# RX8E_ulrich.net
KiCad netlist of a schematic drawn in EAGLE
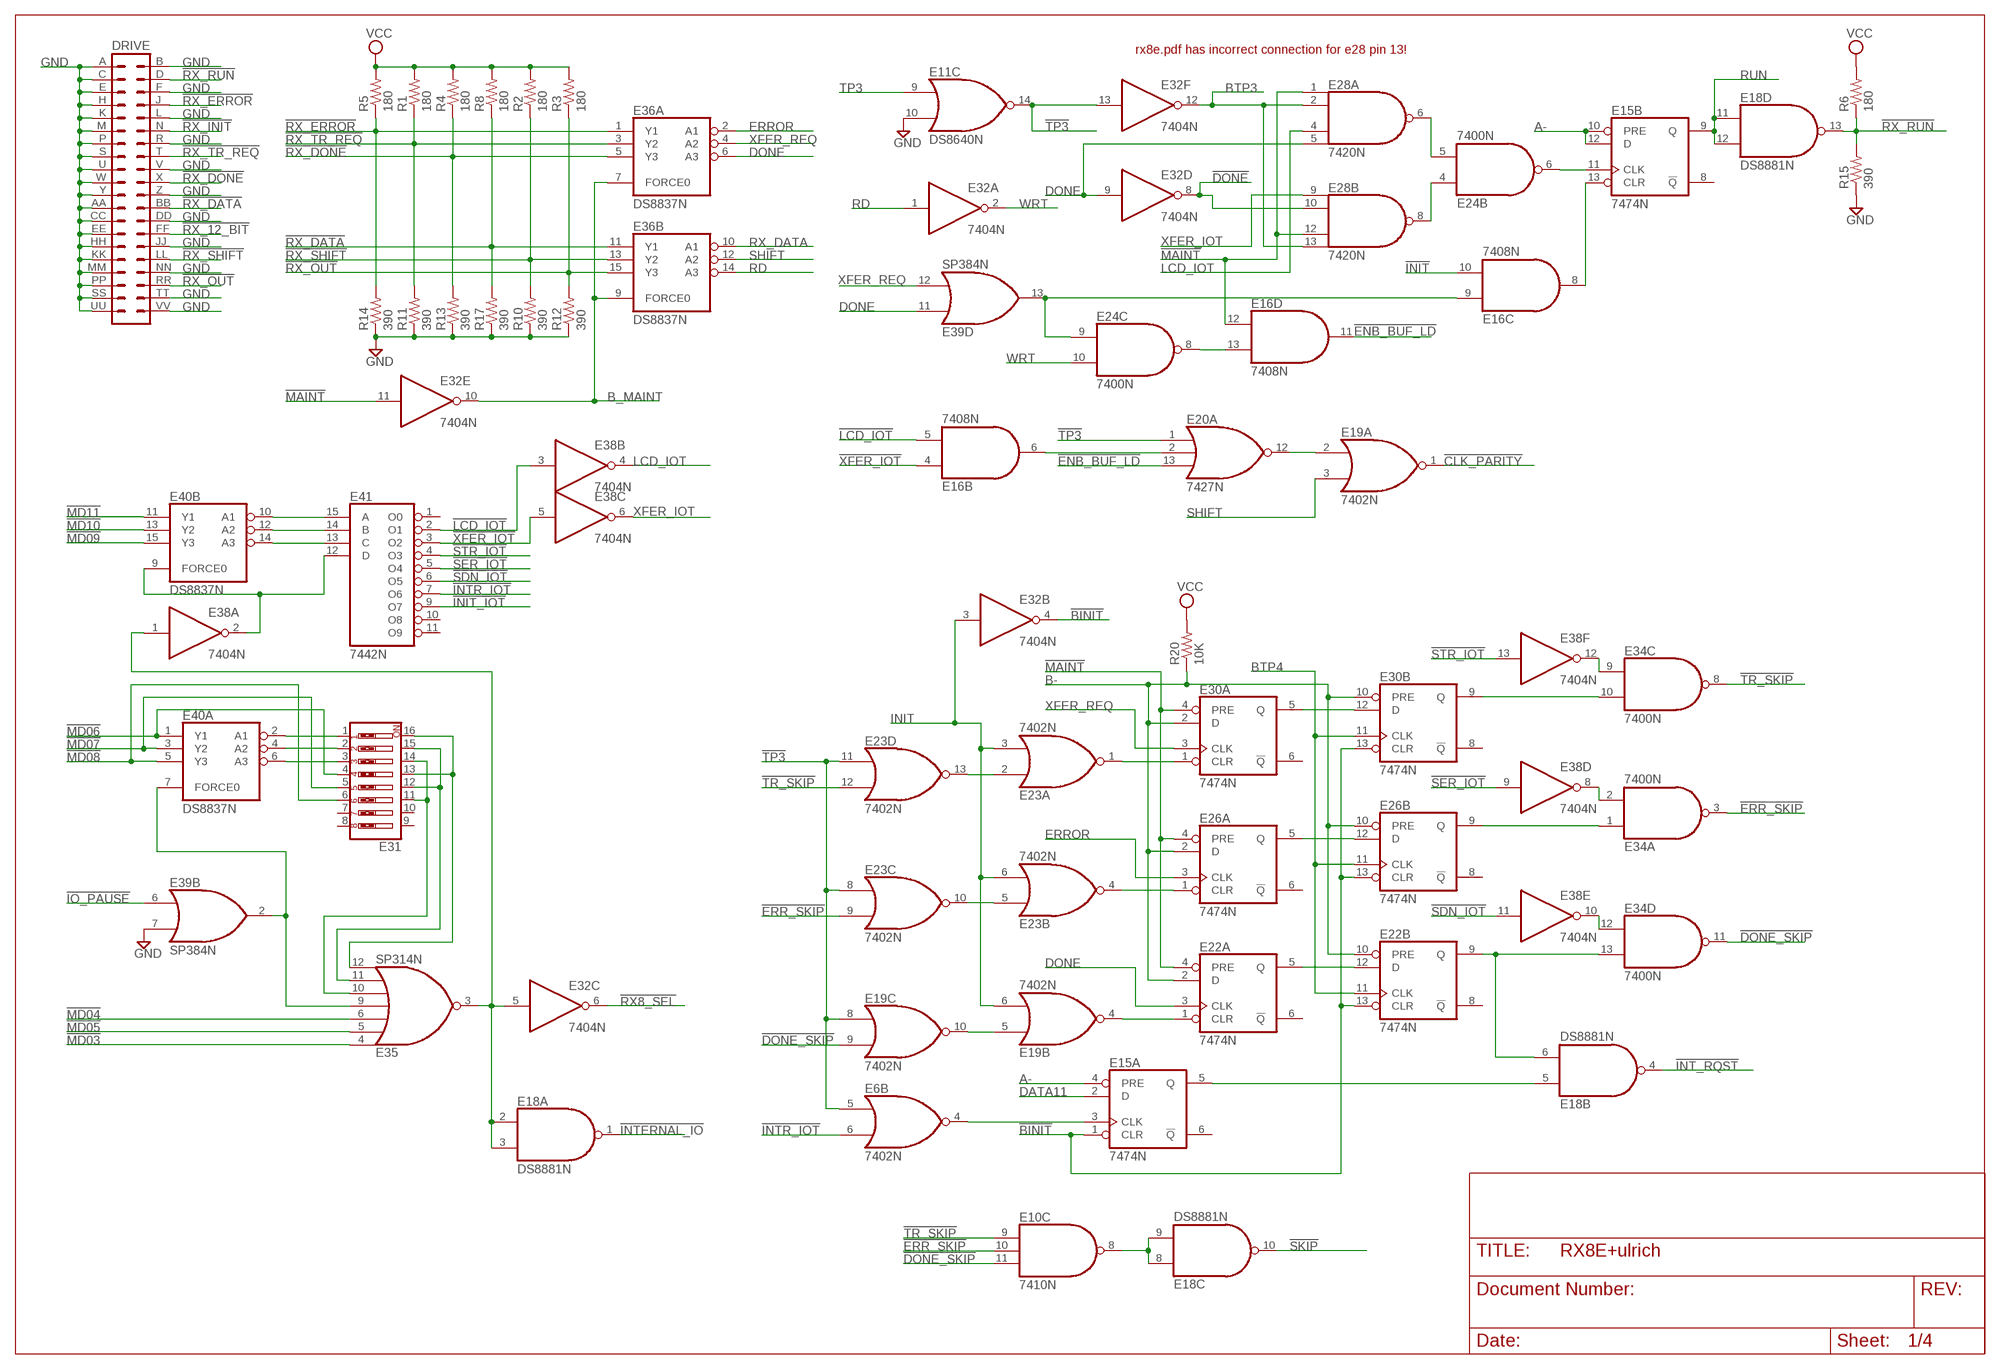
[diagram p0: schematic, sheet 1]
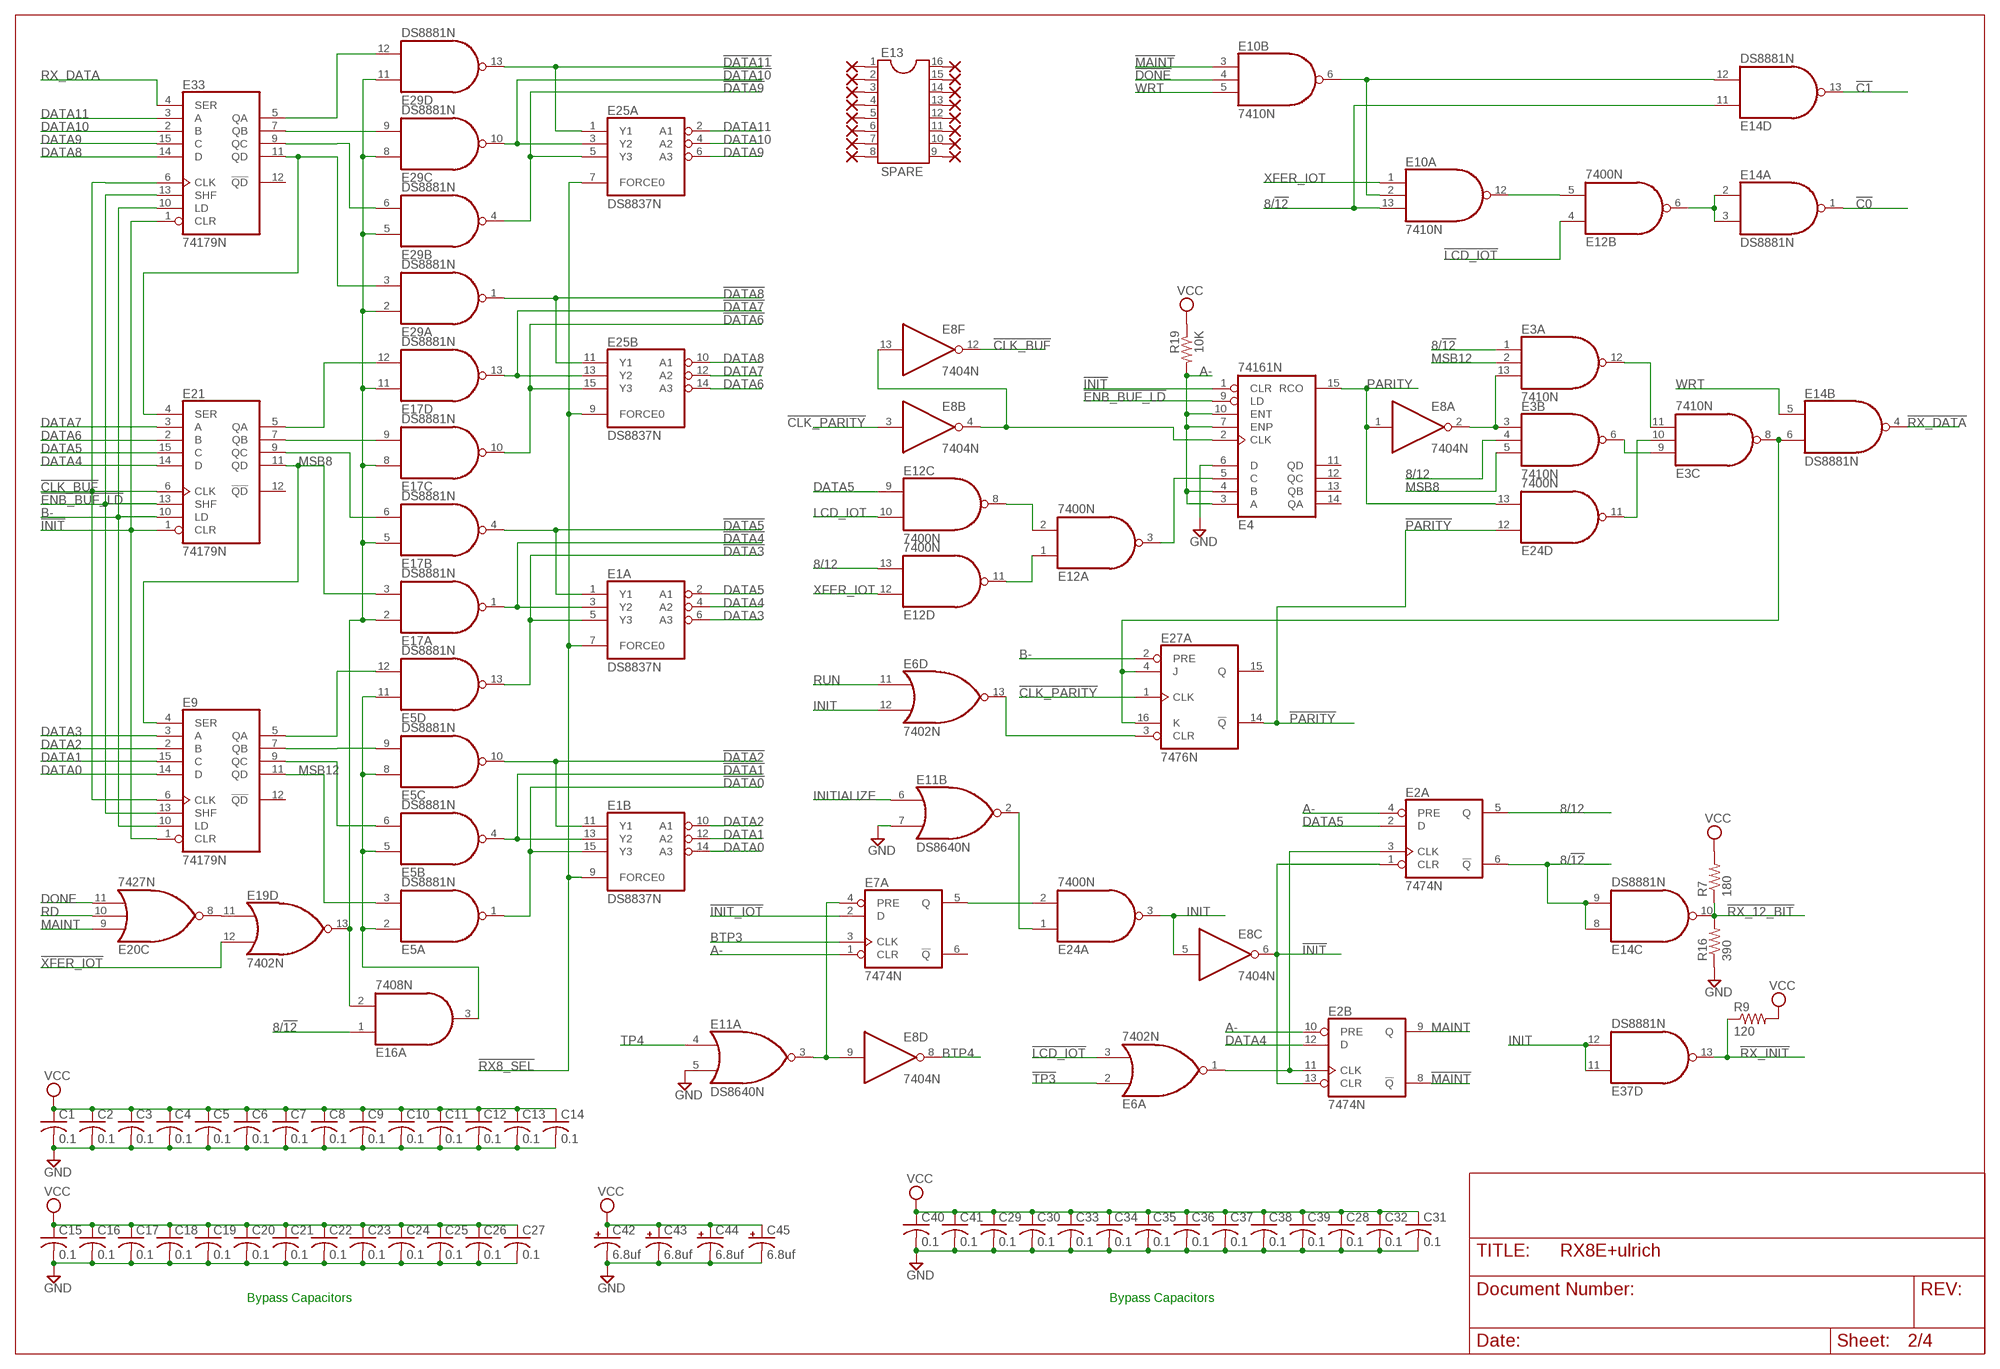
[diagram p1: schematic, sheet 2]
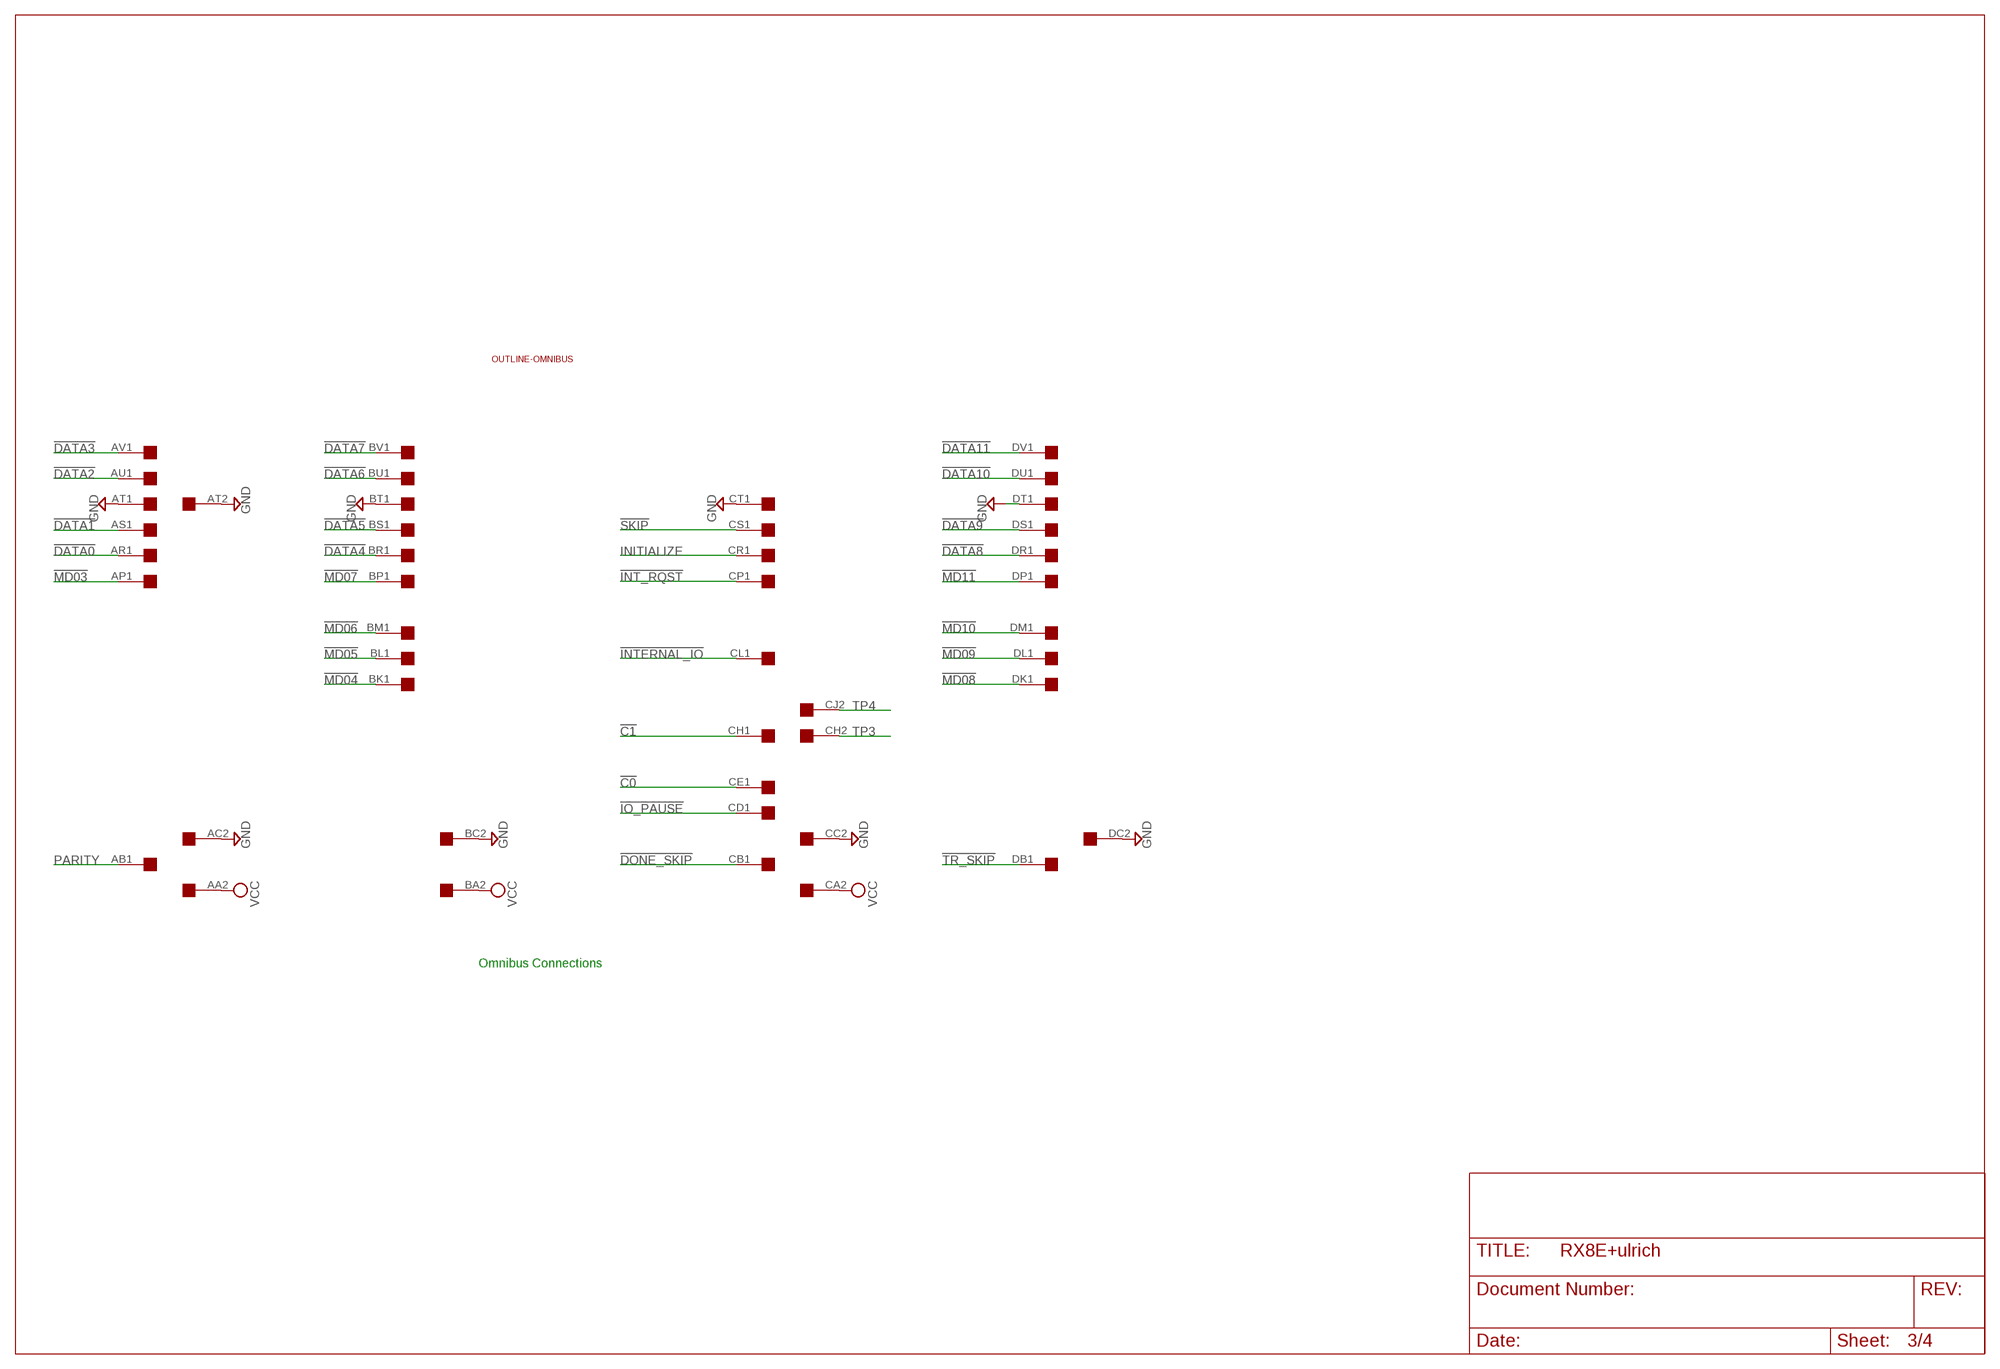
[diagram p2: schematic, sheet 3]
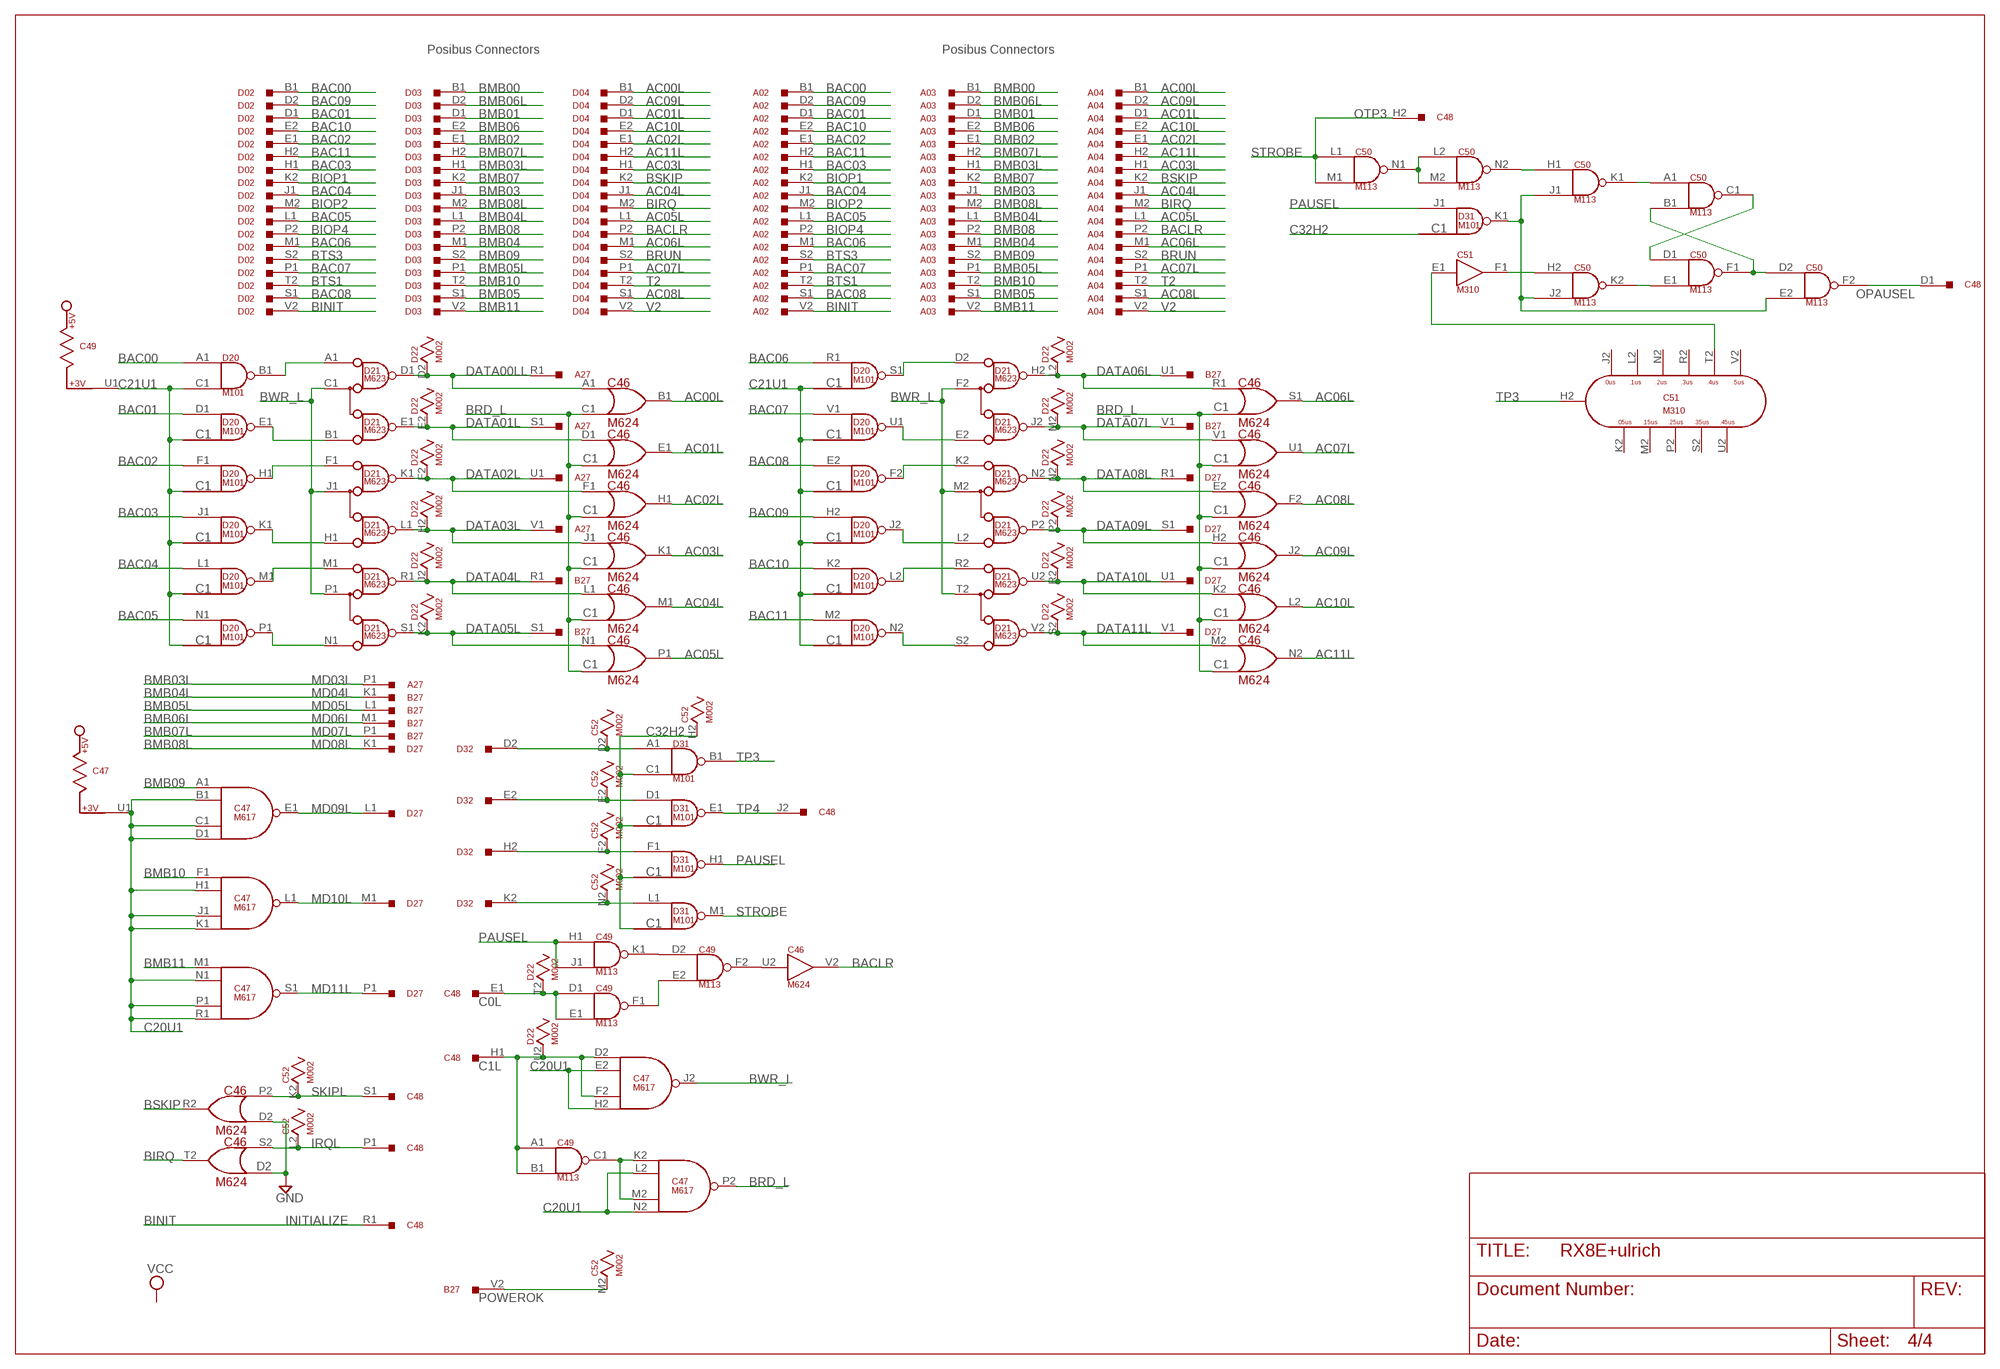
[diagram p3: schematic, sheet 4]

(export (version "E")
  (design (tool "Eeschema 10.0.6"))
  (components
    (comp (ref "C1")
      (value "0.1")
      (footprint "eagle-import:C050-025X075")
      (libsource (lib "eagle-import") (part "C-US050-025X075"))
    )
    (comp (ref "C2")
      (value "0.1")
      (footprint "eagle-import:C050-025X075")
      (libsource (lib "eagle-import") (part "C-US050-025X075"))
    )
    (comp (ref "C3")
      (value "0.1")
      (footprint "eagle-import:C050-025X075")
      (libsource (lib "eagle-import") (part "C-US050-025X075"))
    )
    (comp (ref "C4")
      (value "0.1")
      (footprint "eagle-import:C050-025X075")
      (libsource (lib "eagle-import") (part "C-US050-025X075"))
    )
    (comp (ref "C5")
      (value "0.1")
      (footprint "eagle-import:C050-025X075")
      (libsource (lib "eagle-import") (part "C-US050-025X075"))
    )
    (comp (ref "C6")
      (value "0.1")
      (footprint "eagle-import:C050-025X075")
      (libsource (lib "eagle-import") (part "C-US050-025X075"))
    )
    (comp (ref "C7")
      (value "0.1")
      (footprint "eagle-import:C050-025X075")
      (libsource (lib "eagle-import") (part "C-US050-025X075"))
    )
    (comp (ref "C8")
      (value "0.1")
      (footprint "eagle-import:C050-025X075")
      (libsource (lib "eagle-import") (part "C-US050-025X075"))
    )
    (comp (ref "C9")
      (value "0.1")
      (footprint "eagle-import:C050-025X075")
      (libsource (lib "eagle-import") (part "C-US050-025X075"))
    )
    (comp (ref "C10")
      (value "0.1")
      (footprint "eagle-import:C050-025X075")
      (libsource (lib "eagle-import") (part "C-US050-025X075"))
    )
    (comp (ref "C11")
      (value "0.1")
      (footprint "eagle-import:C050-025X075")
      (libsource (lib "eagle-import") (part "C-US050-025X075"))
    )
    (comp (ref "C12")
      (value "0.1")
      (footprint "eagle-import:C050-025X075")
      (libsource (lib "eagle-import") (part "C-US050-025X075"))
    )
    (comp (ref "C13")
      (value "0.1")
      (footprint "eagle-import:C050-025X075")
      (libsource (lib "eagle-import") (part "C-US050-025X075"))
    )
    (comp (ref "C14")
      (value "0.1")
      (footprint "eagle-import:C050-025X075")
      (libsource (lib "eagle-import") (part "C-US050-025X075"))
    )
    (comp (ref "C15")
      (value "0.1")
      (footprint "eagle-import:C050-025X075")
      (libsource (lib "eagle-import") (part "C-US050-025X075"))
    )
    (comp (ref "C16")
      (value "0.1")
      (footprint "eagle-import:C050-025X075")
      (libsource (lib "eagle-import") (part "C-US050-025X075"))
    )
    (comp (ref "C17")
      (value "0.1")
      (footprint "eagle-import:C050-025X075")
      (libsource (lib "eagle-import") (part "C-US050-025X075"))
    )
    (comp (ref "C18")
      (value "0.1")
      (footprint "eagle-import:C050-025X075")
      (libsource (lib "eagle-import") (part "C-US050-025X075"))
    )
    (comp (ref "C19")
      (value "0.1")
      (footprint "eagle-import:C050-025X075")
      (libsource (lib "eagle-import") (part "C-US050-025X075"))
    )
    (comp (ref "C20")
      (value "0.1")
      (footprint "eagle-import:C050-025X075")
      (libsource (lib "eagle-import") (part "C-US050-025X075"))
    )
    (comp (ref "C21")
      (value "0.1")
      (footprint "eagle-import:C050-025X075")
      (libsource (lib "eagle-import") (part "C-US050-025X075"))
    )
    (comp (ref "C22")
      (value "0.1")
      (footprint "eagle-import:C050-025X075")
      (libsource (lib "eagle-import") (part "C-US050-025X075"))
    )
    (comp (ref "C23")
      (value "0.1")
      (footprint "eagle-import:C050-025X075")
      (libsource (lib "eagle-import") (part "C-US050-025X075"))
    )
    (comp (ref "C24")
      (value "0.1")
      (footprint "eagle-import:C050-025X075")
      (libsource (lib "eagle-import") (part "C-US050-025X075"))
    )
    (comp (ref "C25")
      (value "0.1")
      (footprint "eagle-import:C050-025X075")
      (libsource (lib "eagle-import") (part "C-US050-025X075"))
    )
    (comp (ref "C26")
      (value "0.1")
      (footprint "eagle-import:C050-025X075")
      (libsource (lib "eagle-import") (part "C-US050-025X075"))
    )
    (comp (ref "C27")
      (value "0.1")
      (footprint "eagle-import:C050-025X075")
      (libsource (lib "eagle-import") (part "C-US050-025X075"))
    )
    (comp (ref "C28")
      (value "0.1")
      (footprint "eagle-import:C050-025X075")
      (libsource (lib "eagle-import") (part "C-US050-025X075"))
    )
    (comp (ref "C29")
      (value "0.1")
      (footprint "eagle-import:C050-025X075")
      (libsource (lib "eagle-import") (part "C-US050-025X075"))
    )
    (comp (ref "C30")
      (value "0.1")
      (footprint "eagle-import:C050-025X075")
      (libsource (lib "eagle-import") (part "C-US050-025X075"))
    )
    (comp (ref "C31")
      (value "0.1")
      (footprint "eagle-import:C050-025X075")
      (libsource (lib "eagle-import") (part "C-US050-025X075"))
    )
    (comp (ref "C32")
      (value "0.1")
      (footprint "eagle-import:C050-025X075")
      (libsource (lib "eagle-import") (part "C-US050-025X075"))
    )
    (comp (ref "C33")
      (value "0.1")
      (footprint "eagle-import:C050-025X075")
      (libsource (lib "eagle-import") (part "C-US050-025X075"))
    )
    (comp (ref "C34")
      (value "0.1")
      (footprint "eagle-import:C050-025X075")
      (libsource (lib "eagle-import") (part "C-US050-025X075"))
    )
    (comp (ref "C35")
      (value "0.1")
      (footprint "eagle-import:C050-025X075")
      (libsource (lib "eagle-import") (part "C-US050-025X075"))
    )
    (comp (ref "C36")
      (value "0.1")
      (footprint "eagle-import:C050-025X075")
      (libsource (lib "eagle-import") (part "C-US050-025X075"))
    )
    (comp (ref "C37")
      (value "0.1")
      (footprint "eagle-import:C050-025X075")
      (libsource (lib "eagle-import") (part "C-US050-025X075"))
    )
    (comp (ref "C38")
      (value "0.1")
      (footprint "eagle-import:C050-025X075")
      (libsource (lib "eagle-import") (part "C-US050-025X075"))
    )
    (comp (ref "C39")
      (value "0.1")
      (footprint "eagle-import:C050-025X075")
      (libsource (lib "eagle-import") (part "C-US050-025X075"))
    )
    (comp (ref "C40")
      (value "0.1")
      (footprint "eagle-import:C050-025X075")
      (libsource (lib "eagle-import") (part "C-US050-025X075"))
    )
    (comp (ref "C41")
      (value "0.1")
      (footprint "eagle-import:C050-025X075")
      (libsource (lib "eagle-import") (part "C-US050-025X075"))
    )
    (comp (ref "C42")
      (value "6.8uf")
      (footprint "eagle-import:E22-6")
      (libsource (lib "eagle-import") (part "CPOL-USE22-6AXIAL"))
    )
    (comp (ref "C43")
      (value "6.8uf")
      (footprint "eagle-import:E22-6")
      (libsource (lib "eagle-import") (part "CPOL-USE22-6AXIAL"))
    )
    (comp (ref "C44")
      (value "6.8uf")
      (footprint "eagle-import:E22-6")
      (libsource (lib "eagle-import") (part "CPOL-USE22-6AXIAL"))
    )
    (comp (ref "C45")
      (value "6.8uf")
      (footprint "eagle-import:E22-6")
      (libsource (lib "eagle-import") (part "CPOL-USE22-6AXIAL"))
    )
    (comp (ref "E1")
      (value "DS8837N")
      (footprint "eagle-import:DIL16")
      (libsource (lib "eagle-import") (part "DS8837N"))
    )
    (comp (ref "E2")
      (value "7474N")
      (footprint "eagle-import:DIL14")
      (libsource (lib "eagle-import") (part "7474NLS"))
    )
    (comp (ref "E3")
      (value "7410N")
      (footprint "eagle-import:DIL14")
      (libsource (lib "eagle-import") (part "7410NLS"))
    )
    (comp (ref "E4")
      (value "74161N")
      (footprint "eagle-import:DIL16")
      (libsource (lib "eagle-import") (part "74161N"))
    )
    (comp (ref "E5")
      (value "DS8881N")
      (footprint "eagle-import:DIL14")
      (libsource (lib "eagle-import") (part "7401NLS"))
    )
    (comp (ref "E6")
      (value "7402N")
      (footprint "eagle-import:DIL14")
      (libsource (lib "eagle-import") (part "7402NLS"))
    )
    (comp (ref "E7")
      (value "7474N")
      (footprint "eagle-import:DIL14")
      (libsource (lib "eagle-import") (part "7474NLS"))
    )
    (comp (ref "E8")
      (value "7404N")
      (footprint "eagle-import:DIL14")
      (libsource (lib "eagle-import") (part "7404NLS"))
    )
    (comp (ref "E9")
      (value "74179N")
      (footprint "eagle-import:DIL16")
      (libsource (lib "eagle-import") (part "74179N"))
    )
    (comp (ref "E10")
      (value "7410N")
      (footprint "eagle-import:DIL14")
      (libsource (lib "eagle-import") (part "7410NLS"))
    )
    (comp (ref "E11")
      (value "DS8640N")
      (footprint "eagle-import:DIL14")
      (libsource (lib "eagle-import") (part "DS8640N"))
    )
    (comp (ref "E12")
      (value "7400N")
      (footprint "eagle-import:DIL14")
      (libsource (lib "eagle-import") (part "7400NLS"))
    )
    (comp (ref "E13")
      (value "SPARE")
      (footprint "eagle-import:DIL16")
      (libsource (lib "eagle-import") (part "DIL16"))
    )
    (comp (ref "E14")
      (value "DS8881N")
      (footprint "eagle-import:DIL14")
      (libsource (lib "eagle-import") (part "7401NLS"))
    )
    (comp (ref "E16")
      (value "7408N")
      (footprint "eagle-import:DIL14")
      (libsource (lib "eagle-import") (part "7408NLS"))
    )
    (comp (ref "E17")
      (value "DS8881N")
      (footprint "eagle-import:DIL14")
      (libsource (lib "eagle-import") (part "7401NLS"))
    )
    (comp (ref "E19")
      (value "7402N")
      (footprint "eagle-import:DIL14")
      (libsource (lib "eagle-import") (part "7402NLS"))
    )
    (comp (ref "E20")
      (value "7427N")
      (footprint "eagle-import:DIL14")
      (libsource (lib "eagle-import") (part "7427NLS"))
    )
    (comp (ref "E21")
      (value "74179N")
      (footprint "eagle-import:DIL16")
      (libsource (lib "eagle-import") (part "74179N"))
    )
    (comp (ref "E24")
      (value "7400N")
      (footprint "eagle-import:DIL14")
      (libsource (lib "eagle-import") (part "7400NLS"))
    )
    (comp (ref "E25")
      (value "DS8837N")
      (footprint "eagle-import:DIL16")
      (libsource (lib "eagle-import") (part "DS8837N"))
    )
    (comp (ref "E27")
      (value "7476N")
      (footprint "eagle-import:DIL16")
      (libsource (lib "eagle-import") (part "7476N"))
    )
    (comp (ref "E29")
      (value "DS8881N")
      (footprint "eagle-import:DIL14")
      (libsource (lib "eagle-import") (part "7401NLS"))
    )
    (comp (ref "E33")
      (value "74179N")
      (footprint "eagle-import:DIL16")
      (libsource (lib "eagle-import") (part "74179N"))
    )
    (comp (ref "E37")
      (value "DS8881N")
      (footprint "eagle-import:DIL14")
      (libsource (lib "eagle-import") (part "7401NLS"))
    )
    (comp (ref "PAD10")
      (value "1,6/0,8")
      (footprint "eagle-import:1,6_0,8")
      (libsource (lib "eagle-import") (part "1,6/0,8"))
    )
    (comp (ref "PAD11")
      (value "1,6/0,8")
      (footprint "eagle-import:1,6_0,8")
      (libsource (lib "eagle-import") (part "1,6/0,8"))
    )
    (comp (ref "PAD12")
      (value "1,6/0,8")
      (footprint "eagle-import:1,6_0,8")
      (libsource (lib "eagle-import") (part "1,6/0,8"))
    )
    (comp (ref "PAD13")
      (value "1,6/0,8")
      (footprint "eagle-import:1,6_0,8")
      (libsource (lib "eagle-import") (part "1,6/0,8"))
    )
    (comp (ref "PAD14")
      (value "1,6/0,8")
      (footprint "eagle-import:1,6_0,8")
      (libsource (lib "eagle-import") (part "1,6/0,8"))
    )
    (comp (ref "PAD15")
      (value "1,6/0,8")
      (footprint "eagle-import:1,6_0,8")
      (libsource (lib "eagle-import") (part "1,6/0,8"))
    )
    (comp (ref "PAD16")
      (value "1,6/0,8")
      (footprint "eagle-import:1,6_0,8")
      (libsource (lib "eagle-import") (part "1,6/0,8"))
    )
    (comp (ref "PAD17")
      (value "1,6/0,8")
      (footprint "eagle-import:1,6_0,8")
      (libsource (lib "eagle-import") (part "1,6/0,8"))
    )
    (comp (ref "PAD20")
      (value "1,6/0,8")
      (footprint "eagle-import:1,6_0,8")
      (libsource (lib "eagle-import") (part "1,6/0,8"))
    )
    (comp (ref "PAD21")
      (value "1,6/0,8")
      (footprint "eagle-import:1,6_0,8")
      (libsource (lib "eagle-import") (part "1,6/0,8"))
    )
    (comp (ref "PAD22")
      (value "1,6/0,8")
      (footprint "eagle-import:1,6_0,8")
      (libsource (lib "eagle-import") (part "1,6/0,8"))
    )
    (comp (ref "PAD23")
      (value "1,6/0,8")
      (footprint "eagle-import:1,6_0,8")
      (libsource (lib "eagle-import") (part "1,6/0,8"))
    )
    (comp (ref "PAD24")
      (value "1,6/0,8")
      (footprint "eagle-import:1,6_0,8")
      (libsource (lib "eagle-import") (part "1,6/0,8"))
    )
    (comp (ref "PAD25")
      (value "1,6/0,8")
      (footprint "eagle-import:1,6_0,8")
      (libsource (lib "eagle-import") (part "1,6/0,8"))
    )
    (comp (ref "PAD26")
      (value "1,6/0,8")
      (footprint "eagle-import:1,6_0,8")
      (libsource (lib "eagle-import") (part "1,6/0,8"))
    )
    (comp (ref "PAD27")
      (value "1,6/0,8")
      (footprint "eagle-import:1,6_0,8")
      (libsource (lib "eagle-import") (part "1,6/0,8"))
    )
    (comp (ref "R7")
      (value "180")
      (footprint "eagle-import:0207_10")
      (libsource (lib "eagle-import") (part "R-US_0207/10"))
    )
    (comp (ref "R9")
      (value "120")
      (footprint "eagle-import:0207_10")
      (libsource (lib "eagle-import") (part "R-US_0207/10"))
    )
    (comp (ref "R16")
      (value "390")
      (footprint "eagle-import:0207_10")
      (libsource (lib "eagle-import") (part "R-US_0207/10"))
    )
    (comp (ref "R19")
      (value "10K")
      (footprint "eagle-import:0207_10")
      (libsource (lib "eagle-import") (part "R-US_0207/10"))
    )
    (comp (ref "U$2")
      (value "QUAD")
      (footprint "eagle-import:EDGE-CON8")
      (libsource (lib "eagle-import") (part "QUAD"))
    )
    (comp (ref "U$5")
      (value "OUTLINE-OMNIBUS")
      (footprint "eagle-import:OMNIBUS")
      (libsource (lib "eagle-import") (part "OUTLINE-OMNIBUS"))
    )
    (comp (ref "DRIVE")
      (value "DEC40PINH")
      (footprint "eagle-import:DEC40PINH")
      (libsource (lib "eagle-import") (part "DEC40PINH"))
    )
    (comp (ref "E15")
      (value "7474N")
      (footprint "eagle-import:DIL14")
      (libsource (lib "eagle-import") (part "7474NLS"))
    )
    (comp (ref "E18")
      (value "DS8881N")
      (footprint "eagle-import:DIL14")
      (libsource (lib "eagle-import") (part "7401NLS"))
    )
    (comp (ref "E22")
      (value "7474N")
      (footprint "eagle-import:DIL14")
      (libsource (lib "eagle-import") (part "7474NLS"))
    )
    (comp (ref "E23")
      (value "7402N")
      (footprint "eagle-import:DIL14")
      (libsource (lib "eagle-import") (part "7402NLS"))
    )
    (comp (ref "E26")
      (value "7474N")
      (footprint "eagle-import:DIL14")
      (libsource (lib "eagle-import") (part "7474NLS"))
    )
    (comp (ref "E28")
      (value "7420N")
      (footprint "eagle-import:DIL14")
      (libsource (lib "eagle-import") (part "7420NLS"))
    )
    (comp (ref "E30")
      (value "7474N")
      (footprint "eagle-import:DIL14")
      (libsource (lib "eagle-import") (part "7474NLS"))
    )
    (comp (ref "E31")
      (value "SW_DIP-8")
      (footprint "eagle-import:EDG-08")
      (libsource (lib "eagle-import") (part "SW_DIP-8"))
    )
    (comp (ref "E32")
      (value "7404N")
      (footprint "eagle-import:DIL14")
      (libsource (lib "eagle-import") (part "7404NLS"))
    )
    (comp (ref "E34")
      (value "7400N")
      (footprint "eagle-import:DIL14")
      (libsource (lib "eagle-import") (part "7400N"))
    )
    (comp (ref "E35")
      (value "SP314N")
      (footprint "eagle-import:DIL14")
      (libsource (lib "eagle-import") (part "SP314N"))
    )
    (comp (ref "E36")
      (value "DS8837N")
      (footprint "eagle-import:DIL16")
      (libsource (lib "eagle-import") (part "DS8837N"))
    )
    (comp (ref "E38")
      (value "7404N")
      (footprint "eagle-import:DIL14")
      (libsource (lib "eagle-import") (part "7404NLS"))
    )
    (comp (ref "E39")
      (value "SP384N")
      (footprint "eagle-import:DIL14")
      (libsource (lib "eagle-import") (part "SP384N"))
    )
    (comp (ref "E40")
      (value "DS8837N")
      (footprint "eagle-import:DIL16")
      (libsource (lib "eagle-import") (part "DS8837N"))
    )
    (comp (ref "E41")
      (value "7442N")
      (footprint "eagle-import:DIL16")
      (libsource (lib "eagle-import") (part "7442NLS"))
    )
    (comp (ref "R1")
      (value "180")
      (footprint "eagle-import:0207_10")
      (libsource (lib "eagle-import") (part "R-US_0207/10"))
    )
    (comp (ref "R2")
      (value "180")
      (footprint "eagle-import:0207_10")
      (libsource (lib "eagle-import") (part "R-US_0207/10"))
    )
    (comp (ref "R3")
      (value "180")
      (footprint "eagle-import:0207_10")
      (libsource (lib "eagle-import") (part "R-US_0207/10"))
    )
    (comp (ref "R4")
      (value "180")
      (footprint "eagle-import:0207_10")
      (libsource (lib "eagle-import") (part "R-US_0207/10"))
    )
    (comp (ref "R5")
      (value "180")
      (footprint "eagle-import:0207_10")
      (libsource (lib "eagle-import") (part "R-US_0207/10"))
    )
    (comp (ref "R6")
      (value "180")
      (footprint "eagle-import:0207_10")
      (libsource (lib "eagle-import") (part "R-US_0207/10"))
    )
    (comp (ref "R8")
      (value "180")
      (footprint "eagle-import:0207_10")
      (libsource (lib "eagle-import") (part "R-US_0207/10"))
    )
    (comp (ref "R10")
      (value "390")
      (footprint "eagle-import:0207_10")
      (libsource (lib "eagle-import") (part "R-US_0207/10"))
    )
    (comp (ref "R11")
      (value "390")
      (footprint "eagle-import:0207_10")
      (libsource (lib "eagle-import") (part "R-US_0207/10"))
    )
    (comp (ref "R12")
      (value "390")
      (footprint "eagle-import:0207_10")
      (libsource (lib "eagle-import") (part "R-US_0207/10"))
    )
    (comp (ref "R13")
      (value "390")
      (footprint "eagle-import:0207_10")
      (libsource (lib "eagle-import") (part "R-US_0207/10"))
    )
    (comp (ref "R14")
      (value "390")
      (footprint "eagle-import:0207_10")
      (libsource (lib "eagle-import") (part "R-US_0207/10"))
    )
    (comp (ref "R15")
      (value "390")
      (footprint "eagle-import:0207_10")
      (libsource (lib "eagle-import") (part "R-US_0207/10"))
    )
    (comp (ref "R17")
      (value "390")
      (footprint "eagle-import:0207_10")
      (libsource (lib "eagle-import") (part "R-US_0207/10"))
    )
    (comp (ref "R20")
      (value "10K")
      (footprint "eagle-import:0207_10")
      (libsource (lib "eagle-import") (part "R-US_0207/10"))
    )
    (comp (ref "A02")
      (value "M903")
      (footprint "eagle-import:H807")
      (libsource (lib "eagle-import") (part "M903"))
    )
    (comp (ref "A03")
      (value "M903")
      (footprint "eagle-import:H807")
      (libsource (lib "eagle-import") (part "M903"))
    )
    (comp (ref "A04")
      (value "M903")
      (footprint "eagle-import:H807")
      (libsource (lib "eagle-import") (part "M903"))
    )
    (comp (ref "A27")
      (value "M916")
      (footprint "eagle-import:H807")
      (libsource (lib "eagle-import") (part "M916"))
    )
    (comp (ref "B27")
      (value "M916")
      (footprint "eagle-import:H807")
      (libsource (lib "eagle-import") (part "M916"))
    )
    (comp (ref "C46")
      (value "M624")
      (footprint "eagle-import:H807")
      (libsource (lib "eagle-import") (part "M624"))
    )
    (comp (ref "C47")
      (value "M617")
      (footprint "eagle-import:H807")
      (libsource (lib "eagle-import") (part "M617"))
    )
    (comp (ref "C48")
      (value "M916")
      (footprint "eagle-import:H807")
      (libsource (lib "eagle-import") (part "M916"))
    )
    (comp (ref "C49")
      (value "M113")
      (footprint "eagle-import:H807")
      (libsource (lib "eagle-import") (part "M113"))
    )
    (comp (ref "C50")
      (value "M113")
      (footprint "eagle-import:H807")
      (libsource (lib "eagle-import") (part "M113"))
    )
    (comp (ref "C51")
      (value "M310")
      (footprint "eagle-import:H807")
      (libsource (lib "eagle-import") (part "M310"))
    )
    (comp (ref "C52")
      (value "M002")
      (footprint "eagle-import:H807")
      (libsource (lib "eagle-import") (part "M002"))
    )
    (comp (ref "D02")
      (value "M903")
      (footprint "eagle-import:H807")
      (libsource (lib "eagle-import") (part "M903"))
    )
    (comp (ref "D03")
      (value "M903")
      (footprint "eagle-import:H807")
      (libsource (lib "eagle-import") (part "M903"))
    )
    (comp (ref "D04")
      (value "M903")
      (footprint "eagle-import:H807")
      (libsource (lib "eagle-import") (part "M903"))
    )
    (comp (ref "D20")
      (value "M101")
      (footprint "eagle-import:H807")
      (libsource (lib "eagle-import") (part "M101"))
    )
    (comp (ref "D21")
      (value "M623")
      (footprint "eagle-import:H807")
      (libsource (lib "eagle-import") (part "M623"))
    )
    (comp (ref "D22")
      (value "M002")
      (footprint "eagle-import:H807")
      (libsource (lib "eagle-import") (part "M002"))
    )
    (comp (ref "D27")
      (value "M916")
      (footprint "eagle-import:H807")
      (libsource (lib "eagle-import") (part "M916"))
    )
    (comp (ref "D31")
      (value "M101")
      (footprint "eagle-import:H807")
      (libsource (lib "eagle-import") (part "M101"))
    )
    (comp (ref "D32")
      (value "M903")
      (footprint "eagle-import:H807")
      (libsource (lib "eagle-import") (part "M903"))
    )
  )
  (nets
    (net (code "1") (name "8{slash}12") (class "Default")
      (node (ref "E12") (pin "13") (pinfunction "I1_13") (pintype "input"))
      (node (ref "E2") (pin "5") (pinfunction "Q_5") (pintype "output"))
      (node (ref "E3") (pin "4") (pinfunction "I1_4") (pintype "input"))
    )
    (net (code "2") (name "8{slash}~{12}") (class "Default")
      (node (ref "E10") (pin "13") (pinfunction "I2_13") (pintype "input"))
      (node (ref "E14") (pin "11") (pinfunction "I0_11") (pintype "input"))
      (node (ref "E14") (pin "8") (pinfunction "I0_8") (pintype "input"))
      (node (ref "E14") (pin "9") (pinfunction "I1_9") (pintype "input"))
      (node (ref "E16") (pin "1") (pinfunction "I0_1") (pintype "input"))
      (node (ref "E2") (pin "6") (pinfunction "~{Q}_6") (pintype "output"))
      (node (ref "E3") (pin "1") (pinfunction "I0_1") (pintype "input"))
    )
    (net (code "3") (name "A-") (class "Default")
      (node (ref "E15") (pin "10") (pinfunction "PRE_10") (pintype "input"))
      (node (ref "E15") (pin "12") (pinfunction "D_12") (pintype "input"))
      (node (ref "E15") (pin "4") (pinfunction "PRE_4") (pintype "input"))
      (node (ref "E2") (pin "10") (pinfunction "PRE_10") (pintype "input"))
      (node (ref "E2") (pin "4") (pinfunction "PRE_4") (pintype "input"))
      (node (ref "E4") (pin "10") (pinfunction "ENT_10") (pintype "input"))
      (node (ref "E4") (pin "3") (pinfunction "A_3") (pintype "input"))
      (node (ref "E4") (pin "4") (pinfunction "B_4") (pintype "input"))
      (node (ref "E4") (pin "7") (pinfunction "ENP_7") (pintype "input"))
      (node (ref "E7") (pin "1") (pinfunction "CLR_1") (pintype "input"))
      (node (ref "R19") (pin "2") (pinfunction "2_2") (pintype "passive"))
    )
    (net (code "4") (name "AC00L") (class "Default")
      (node (ref "A04") (pin "B1") (pinfunction "P$2_B1") (pintype "bidirectional"))
      (node (ref "C46") (pin "B1") (pinfunction "OUT_B1") (pintype "output"))
      (node (ref "D04") (pin "B1") (pinfunction "P$2_B1") (pintype "bidirectional"))
    )
    (net (code "5") (name "AC01L") (class "Default")
      (node (ref "A04") (pin "D1") (pinfunction "P$2_D1") (pintype "bidirectional"))
      (node (ref "C46") (pin "E1") (pinfunction "OUT_E1") (pintype "output"))
      (node (ref "D04") (pin "D1") (pinfunction "P$2_D1") (pintype "bidirectional"))
    )
    (net (code "6") (name "AC02L") (class "Default")
      (node (ref "A04") (pin "E1") (pinfunction "P$2_E1") (pintype "bidirectional"))
      (node (ref "C46") (pin "H1") (pinfunction "OUT_H1") (pintype "output"))
      (node (ref "D04") (pin "E1") (pinfunction "P$2_E1") (pintype "bidirectional"))
    )
    (net (code "7") (name "AC03L") (class "Default")
      (node (ref "A04") (pin "H1") (pinfunction "P$2_H1") (pintype "bidirectional"))
      (node (ref "C46") (pin "K1") (pinfunction "OUT_K1") (pintype "output"))
      (node (ref "D04") (pin "H1") (pinfunction "P$2_H1") (pintype "bidirectional"))
    )
    (net (code "8") (name "AC04L") (class "Default")
      (node (ref "A04") (pin "J1") (pinfunction "P$2_J1") (pintype "bidirectional"))
      (node (ref "C46") (pin "M1") (pinfunction "OUT_M1") (pintype "output"))
      (node (ref "D04") (pin "J1") (pinfunction "P$2_J1") (pintype "bidirectional"))
    )
    (net (code "9") (name "AC05L") (class "Default")
      (node (ref "A04") (pin "L1") (pinfunction "P$2_L1") (pintype "bidirectional"))
      (node (ref "C46") (pin "P1") (pinfunction "OUT_P1") (pintype "output"))
      (node (ref "D04") (pin "L1") (pinfunction "P$2_L1") (pintype "bidirectional"))
    )
    (net (code "10") (name "AC06L") (class "Default")
      (node (ref "A04") (pin "M1") (pinfunction "P$2_M1") (pintype "bidirectional"))
      (node (ref "C46") (pin "S1") (pinfunction "OUT_S1") (pintype "output"))
      (node (ref "D04") (pin "M1") (pinfunction "P$2_M1") (pintype "bidirectional"))
    )
    (net (code "11") (name "AC07L") (class "Default")
      (node (ref "A04") (pin "P1") (pinfunction "P$2_P1") (pintype "bidirectional"))
      (node (ref "C46") (pin "U1") (pinfunction "OUT_U1") (pintype "output"))
      (node (ref "D04") (pin "P1") (pinfunction "P$2_P1") (pintype "bidirectional"))
    )
    (net (code "12") (name "AC08L") (class "Default")
      (node (ref "A04") (pin "S1") (pinfunction "P$2_S1") (pintype "bidirectional"))
      (node (ref "C46") (pin "F2") (pinfunction "OUT_F2") (pintype "output"))
      (node (ref "D04") (pin "S1") (pinfunction "P$2_S1") (pintype "bidirectional"))
    )
    (net (code "13") (name "AC09L") (class "Default")
      (node (ref "A04") (pin "D2") (pinfunction "P$2_D2") (pintype "bidirectional"))
      (node (ref "C46") (pin "J2") (pinfunction "OUT_J2") (pintype "output"))
      (node (ref "D04") (pin "D2") (pinfunction "P$2_D2") (pintype "bidirectional"))
    )
    (net (code "14") (name "AC10L") (class "Default")
      (node (ref "A04") (pin "E2") (pinfunction "P$2_E2") (pintype "bidirectional"))
      (node (ref "C46") (pin "L2") (pinfunction "OUT_L2") (pintype "output"))
      (node (ref "D04") (pin "E2") (pinfunction "P$2_E2") (pintype "bidirectional"))
    )
    (net (code "15") (name "AC11L") (class "Default")
      (node (ref "A04") (pin "H2") (pinfunction "P$2_H2") (pintype "bidirectional"))
      (node (ref "C46") (pin "N2") (pinfunction "OUT_N2") (pintype "output"))
      (node (ref "D04") (pin "H2") (pinfunction "P$2_H2") (pintype "bidirectional"))
    )
    (net (code "16") (name "B-") (class "Default")
      (node (ref "E21") (pin "10") (pinfunction "LD_10") (pintype "input"))
      (node (ref "E22") (pin "10") (pinfunction "PRE_10") (pintype "input"))
      (node (ref "E22") (pin "2") (pinfunction "D_2") (pintype "input"))
      (node (ref "E26") (pin "10") (pinfunction "PRE_10") (pintype "input"))
      (node (ref "E26") (pin "2") (pinfunction "D_2") (pintype "input"))
      (node (ref "E27") (pin "2") (pinfunction "PRE_2") (pintype "input"))
      (node (ref "E30") (pin "10") (pinfunction "PRE_10") (pintype "input"))
      (node (ref "E30") (pin "2") (pinfunction "D_2") (pintype "input"))
      (node (ref "E33") (pin "10") (pinfunction "LD_10") (pintype "input"))
      (node (ref "E9") (pin "10") (pinfunction "LD_10") (pintype "input"))
      (node (ref "R20") (pin "1") (pinfunction "1_1") (pintype "passive"))
    )
    (net (code "17") (name "BAC00") (class "Default")
      (node (ref "A02") (pin "B1") (pinfunction "P$2_B1") (pintype "bidirectional"))
      (node (ref "D02") (pin "B1") (pinfunction "P$2_B1") (pintype "bidirectional"))
      (node (ref "D20") (pin "A1") (pinfunction "IN1_A1") (pintype "input"))
    )
    (net (code "18") (name "BAC01") (class "Default")
      (node (ref "A02") (pin "D1") (pinfunction "P$2_D1") (pintype "bidirectional"))
      (node (ref "D02") (pin "D1") (pinfunction "P$2_D1") (pintype "bidirectional"))
      (node (ref "D20") (pin "D1") (pinfunction "IN_D1") (pintype "input"))
    )
    (net (code "19") (name "BAC02") (class "Default")
      (node (ref "A02") (pin "E1") (pinfunction "P$2_E1") (pintype "bidirectional"))
      (node (ref "D02") (pin "E1") (pinfunction "P$2_E1") (pintype "bidirectional"))
      (node (ref "D20") (pin "F1") (pinfunction "IN_F1") (pintype "input"))
    )
    (net (code "20") (name "BAC03") (class "Default")
      (node (ref "A02") (pin "H1") (pinfunction "P$2_H1") (pintype "bidirectional"))
      (node (ref "D02") (pin "H1") (pinfunction "P$2_H1") (pintype "bidirectional"))
      (node (ref "D20") (pin "J1") (pinfunction "IN_J1") (pintype "input"))
    )
    (net (code "21") (name "BAC04") (class "Default")
      (node (ref "A02") (pin "J1") (pinfunction "P$2_J1") (pintype "bidirectional"))
      (node (ref "D02") (pin "J1") (pinfunction "P$2_J1") (pintype "bidirectional"))
      (node (ref "D20") (pin "L1") (pinfunction "IN_L1") (pintype "input"))
    )
    (net (code "22") (name "BAC05") (class "Default")
      (node (ref "A02") (pin "L1") (pinfunction "P$2_L1") (pintype "bidirectional"))
      (node (ref "D02") (pin "L1") (pinfunction "P$2_L1") (pintype "bidirectional"))
      (node (ref "D20") (pin "N1") (pinfunction "IN_N1") (pintype "input"))
    )
    (net (code "23") (name "BAC06") (class "Default")
      (node (ref "A02") (pin "M1") (pinfunction "P$2_M1") (pintype "bidirectional"))
      (node (ref "D02") (pin "M1") (pinfunction "P$2_M1") (pintype "bidirectional"))
      (node (ref "D20") (pin "R1") (pinfunction "IN_R1") (pintype "input"))
    )
    (net (code "24") (name "BAC07") (class "Default")
      (node (ref "A02") (pin "P1") (pinfunction "P$2_P1") (pintype "bidirectional"))
      (node (ref "D02") (pin "P1") (pinfunction "P$2_P1") (pintype "bidirectional"))
      (node (ref "D20") (pin "V1") (pinfunction "IN_V1") (pintype "input"))
    )
    (net (code "25") (name "BAC08") (class "Default")
      (node (ref "A02") (pin "S1") (pinfunction "P$2_S1") (pintype "bidirectional"))
      (node (ref "D02") (pin "S1") (pinfunction "P$2_S1") (pintype "bidirectional"))
      (node (ref "D20") (pin "E2") (pinfunction "IN_E2") (pintype "input"))
    )
    (net (code "26") (name "BAC09") (class "Default")
      (node (ref "A02") (pin "D2") (pinfunction "P$2_D2") (pintype "bidirectional"))
      (node (ref "D02") (pin "D2") (pinfunction "P$2_D2") (pintype "bidirectional"))
      (node (ref "D20") (pin "H2") (pinfunction "IN_H2") (pintype "input"))
    )
    (net (code "27") (name "BAC10") (class "Default")
      (node (ref "A02") (pin "E2") (pinfunction "P$2_E2") (pintype "bidirectional"))
      (node (ref "D02") (pin "E2") (pinfunction "P$2_E2") (pintype "bidirectional"))
      (node (ref "D20") (pin "K2") (pinfunction "IN_K2") (pintype "input"))
    )
    (net (code "28") (name "BAC11") (class "Default")
      (node (ref "A02") (pin "H2") (pinfunction "P$2_H2") (pintype "bidirectional"))
      (node (ref "D02") (pin "H2") (pinfunction "P$2_H2") (pintype "bidirectional"))
      (node (ref "D20") (pin "M2") (pinfunction "IN_M2") (pintype "input"))
    )
    (net (code "29") (name "BACLR") (class "Default")
      (node (ref "A04") (pin "P2") (pinfunction "P$2_P2") (pintype "bidirectional"))
      (node (ref "C46") (pin "V2") (pinfunction "OUT_V2") (pintype "output"))
      (node (ref "D04") (pin "P2") (pinfunction "P$2_P2") (pintype "bidirectional"))
    )
    (net (code "30") (name "BINIT") (class "Default")
      (node (ref "A02") (pin "V2") (pinfunction "P$2_V2") (pintype "bidirectional"))
      (node (ref "C48") (pin "R1") (pinfunction "P$2_R1") (pintype "bidirectional"))
      (node (ref "D02") (pin "V2") (pinfunction "P$2_V2") (pintype "bidirectional"))
    )
    (net (code "31") (name "BIOP1") (class "Default")
      (node (ref "A02") (pin "K2") (pinfunction "P$2_K2") (pintype "bidirectional"))
      (node (ref "D02") (pin "K2") (pinfunction "P$2_K2") (pintype "bidirectional"))
    )
    (net (code "32") (name "BIOP2") (class "Default")
      (node (ref "A02") (pin "M2") (pinfunction "P$2_M2") (pintype "bidirectional"))
      (node (ref "D02") (pin "M2") (pinfunction "P$2_M2") (pintype "bidirectional"))
    )
    (net (code "33") (name "BIOP4") (class "Default")
      (node (ref "A02") (pin "P2") (pinfunction "P$2_P2") (pintype "bidirectional"))
      (node (ref "D02") (pin "P2") (pinfunction "P$2_P2") (pintype "bidirectional"))
    )
    (net (code "34") (name "BIRQ") (class "Default")
      (node (ref "A04") (pin "M2") (pinfunction "P$2_M2") (pintype "bidirectional"))
      (node (ref "C46") (pin "T2") (pinfunction "OUT_T2") (pintype "output"))
      (node (ref "D04") (pin "M2") (pinfunction "P$2_M2") (pintype "bidirectional"))
    )
    (net (code "35") (name "BMB00") (class "Default")
      (node (ref "A03") (pin "B1") (pinfunction "P$2_B1") (pintype "bidirectional"))
      (node (ref "D03") (pin "B1") (pinfunction "P$2_B1") (pintype "bidirectional"))
    )
    (net (code "36") (name "BMB01") (class "Default")
      (node (ref "A03") (pin "D1") (pinfunction "P$2_D1") (pintype "bidirectional"))
      (node (ref "D03") (pin "D1") (pinfunction "P$2_D1") (pintype "bidirectional"))
    )
    (net (code "37") (name "BMB02") (class "Default")
      (node (ref "A03") (pin "E1") (pinfunction "P$2_E1") (pintype "bidirectional"))
      (node (ref "D03") (pin "E1") (pinfunction "P$2_E1") (pintype "bidirectional"))
    )
    (net (code "38") (name "BMB03") (class "Default")
      (node (ref "A03") (pin "J1") (pinfunction "P$2_J1") (pintype "bidirectional"))
      (node (ref "D03") (pin "J1") (pinfunction "P$2_J1") (pintype "bidirectional"))
    )
    (net (code "39") (name "BMB03L") (class "Default")
      (node (ref "A03") (pin "H1") (pinfunction "P$2_H1") (pintype "bidirectional"))
      (node (ref "A27") (pin "P1") (pinfunction "P$2_P1") (pintype "bidirectional"))
      (node (ref "D03") (pin "H1") (pinfunction "P$2_H1") (pintype "bidirectional"))
    )
    (net (code "40") (name "BMB04") (class "Default")
      (node (ref "A03") (pin "M1") (pinfunction "P$2_M1") (pintype "bidirectional"))
      (node (ref "D03") (pin "M1") (pinfunction "P$2_M1") (pintype "bidirectional"))
    )
    (net (code "41") (name "BMB04L") (class "Default")
      (node (ref "A03") (pin "L1") (pinfunction "P$2_L1") (pintype "bidirectional"))
      (node (ref "B27") (pin "K1") (pinfunction "P$2_K1") (pintype "bidirectional"))
      (node (ref "D03") (pin "L1") (pinfunction "P$2_L1") (pintype "bidirectional"))
    )
    (net (code "42") (name "BMB05") (class "Default")
      (node (ref "A03") (pin "S1") (pinfunction "P$2_S1") (pintype "bidirectional"))
      (node (ref "D03") (pin "S1") (pinfunction "P$2_S1") (pintype "bidirectional"))
    )
    (net (code "43") (name "BMB05L") (class "Default")
      (node (ref "A03") (pin "P1") (pinfunction "P$2_P1") (pintype "bidirectional"))
      (node (ref "B27") (pin "L1") (pinfunction "P$2_L1") (pintype "bidirectional"))
      (node (ref "D03") (pin "P1") (pinfunction "P$2_P1") (pintype "bidirectional"))
    )
    (net (code "44") (name "BMB06") (class "Default")
      (node (ref "A03") (pin "E2") (pinfunction "P$2_E2") (pintype "bidirectional"))
      (node (ref "D03") (pin "E2") (pinfunction "P$2_E2") (pintype "bidirectional"))
    )
    (net (code "45") (name "BMB06L") (class "Default")
      (node (ref "A03") (pin "D2") (pinfunction "P$2_D2") (pintype "bidirectional"))
      (node (ref "B27") (pin "M1") (pinfunction "P$2_M1") (pintype "bidirectional"))
      (node (ref "D03") (pin "D2") (pinfunction "P$2_D2") (pintype "bidirectional"))
    )
    (net (code "46") (name "BMB07") (class "Default")
      (node (ref "A03") (pin "K2") (pinfunction "P$2_K2") (pintype "bidirectional"))
      (node (ref "D03") (pin "K2") (pinfunction "P$2_K2") (pintype "bidirectional"))
    )
    (net (code "47") (name "BMB07L") (class "Default")
      (node (ref "A03") (pin "H2") (pinfunction "P$2_H2") (pintype "bidirectional"))
      (node (ref "B27") (pin "P1") (pinfunction "P$2_P1") (pintype "bidirectional"))
      (node (ref "D03") (pin "H2") (pinfunction "P$2_H2") (pintype "bidirectional"))
    )
    (net (code "48") (name "BMB08") (class "Default")
      (node (ref "A03") (pin "P2") (pinfunction "P$2_P2") (pintype "bidirectional"))
      (node (ref "D03") (pin "P2") (pinfunction "P$2_P2") (pintype "bidirectional"))
    )
    (net (code "49") (name "BMB08L") (class "Default")
      (node (ref "A03") (pin "M2") (pinfunction "P$2_M2") (pintype "bidirectional"))
      (node (ref "D03") (pin "M2") (pinfunction "P$2_M2") (pintype "bidirectional"))
      (node (ref "D27") (pin "K1") (pinfunction "P$2_K1") (pintype "bidirectional"))
    )
    (net (code "50") (name "BMB09") (class "Default")
      (node (ref "A03") (pin "S2") (pinfunction "P$2_S2") (pintype "bidirectional"))
      (node (ref "C47") (pin "A1") (pinfunction "IN1_A1") (pintype "input"))
      (node (ref "D03") (pin "S2") (pinfunction "P$2_S2") (pintype "bidirectional"))
    )
    (net (code "51") (name "BMB10") (class "Default")
      (node (ref "A03") (pin "T2") (pinfunction "P$2_T2") (pintype "bidirectional"))
      (node (ref "C47") (pin "F1") (pinfunction "IN1_F1") (pintype "input"))
      (node (ref "D03") (pin "T2") (pinfunction "P$2_T2") (pintype "bidirectional"))
    )
    (net (code "52") (name "BMB11") (class "Default")
      (node (ref "A03") (pin "V2") (pinfunction "P$2_V2") (pintype "bidirectional"))
      (node (ref "C47") (pin "M1") (pinfunction "IN1_M1") (pintype "input"))
      (node (ref "D03") (pin "V2") (pinfunction "P$2_V2") (pintype "bidirectional"))
    )
    (net (code "53") (name "BRD_L") (class "Default")
      (node (ref "C46") (pin "C1") (pinfunction "IN2_C1") (pintype "input"))
      (node (ref "C47") (pin "P2") (pinfunction "OUT_P2") (pintype "open_collector"))
    )
    (net (code "54") (name "BRUN") (class "Default")
      (node (ref "A04") (pin "S2") (pinfunction "P$2_S2") (pintype "bidirectional"))
      (node (ref "D04") (pin "S2") (pinfunction "P$2_S2") (pintype "bidirectional"))
    )
    (net (code "55") (name "BSKIP") (class "Default")
      (node (ref "A04") (pin "K2") (pinfunction "P$2_K2") (pintype "bidirectional"))
      (node (ref "C46") (pin "R2") (pinfunction "OUT_R2") (pintype "output"))
      (node (ref "D04") (pin "K2") (pinfunction "P$2_K2") (pintype "bidirectional"))
    )
    (net (code "56") (name "BTP3") (class "Default")
      (node (ref "E28") (pin "13") (pinfunction "I3_13") (pintype "input"))
      (node (ref "E28") (pin "2") (pinfunction "I1_2") (pintype "input"))
      (node (ref "E32") (pin "12") (pinfunction "O_12") (pintype "output"))
      (node (ref "E7") (pin "3") (pinfunction "CLK_3") (pintype "input"))
    )
    (net (code "57") (name "BTP4") (class "Default")
      (node (ref "E22") (pin "11") (pinfunction "CLK_11") (pintype "input"))
      (node (ref "E26") (pin "11") (pinfunction "CLK_11") (pintype "input"))
      (node (ref "E30") (pin "11") (pinfunction "CLK_11") (pintype "input"))
      (node (ref "E8") (pin "8") (pinfunction "O_8") (pintype "output"))
    )
    (net (code "58") (name "BTS1") (class "Default")
      (node (ref "A02") (pin "T2") (pinfunction "P$2_T2") (pintype "bidirectional"))
      (node (ref "D02") (pin "T2") (pinfunction "P$2_T2") (pintype "bidirectional"))
    )
    (net (code "59") (name "BTS3") (class "Default")
      (node (ref "A02") (pin "S2") (pinfunction "P$2_S2") (pintype "bidirectional"))
      (node (ref "D02") (pin "S2") (pinfunction "P$2_S2") (pintype "bidirectional"))
    )
    (net (code "60") (name "BWR_L") (class "Default")
      (node (ref "C47") (pin "J2") (pinfunction "OUT_J2") (pintype "open_collector"))
      (node (ref "D21") (pin "C1") (pinfunction "C_C1") (pintype "input"))
      (node (ref "D21") (pin "F2") (pinfunction "C_F2") (pintype "input"))
      (node (ref "D21") (pin "J1") (pinfunction "C_J1") (pintype "input"))
      (node (ref "D21") (pin "M2") (pinfunction "C_M2") (pintype "input"))
      (node (ref "D21") (pin "P1") (pinfunction "C_P1") (pintype "input"))
      (node (ref "D21") (pin "T2") (pinfunction "C_T2") (pintype "input"))
    )
    (net (code "61") (name "B_MAINT") (class "Default")
      (node (ref "E32") (pin "10") (pinfunction "O_10") (pintype "output"))
      (node (ref "E36") (pin "7") (pinfunction "FORCE0_7") (pintype "input"))
      (node (ref "E36") (pin "9") (pinfunction "FORCE0_9") (pintype "input"))
    )
    (net (code "62") (name "C0L") (class "Default")
      (node (ref "C48") (pin "E1") (pinfunction "P$2_E1") (pintype "bidirectional"))
      (node (ref "C49") (pin "D1") (pinfunction "IN1_D1") (pintype "input"))
      (node (ref "C49") (pin "E1") (pinfunction "IN2_E1") (pintype "input"))
      (node (ref "D22") (pin "T2") (pinfunction "P$1_T2") (pintype "passive"))
    )
    (net (code "63") (name "C1L") (class "Default")
      (node (ref "C47") (pin "D2") (pinfunction "IN1_D2") (pintype "input"))
      (node (ref "C47") (pin "F2") (pinfunction "IN3_F2") (pintype "input"))
      (node (ref "C48") (pin "H1") (pinfunction "P$2_H1") (pintype "bidirectional"))
      (node (ref "C49") (pin "A1") (pinfunction "IN1_A1") (pintype "input"))
      (node (ref "C49") (pin "B1") (pinfunction "IN2_B1") (pintype "input"))
      (node (ref "D22") (pin "U2") (pinfunction "P$1_U2") (pintype "passive"))
    )
    (net (code "64") (name "C20U1") (class "Default")
      (node (ref "C47") (pin "B1") (pinfunction "IN2_B1") (pintype "input"))
      (node (ref "C47") (pin "C1") (pinfunction "IN3_C1") (pintype "input"))
      (node (ref "C47") (pin "D1") (pinfunction "IN4_D1") (pintype "input"))
      (node (ref "C47") (pin "E2") (pinfunction "IN2_E2") (pintype "input"))
      (node (ref "C47") (pin "H1") (pinfunction "IN2_H1") (pintype "input"))
      (node (ref "C47") (pin "H2") (pinfunction "IN4_H2") (pintype "input"))
      (node (ref "C47") (pin "J1") (pinfunction "IN3_J1") (pintype "input"))
      (node (ref "C47") (pin "K1") (pinfunction "IN4_K1") (pintype "input"))
      (node (ref "C47") (pin "L2") (pinfunction "IN2_L2") (pintype "input"))
      (node (ref "C47") (pin "N1") (pinfunction "IN2_N1") (pintype "input"))
      (node (ref "C47") (pin "N2") (pinfunction "IN4_N2") (pintype "input"))
      (node (ref "C47") (pin "P1") (pinfunction "IN3_P1") (pintype "input"))
      (node (ref "C47") (pin "R1") (pinfunction "IN4_R1") (pintype "input"))
      (node (ref "C47") (pin "U1") (pinfunction "P$1_U1") (pintype "passive"))
    )
    (net (code "65") (name "C21U1") (class "Default")
      (node (ref "C49") (pin "U1") (pinfunction "P$1_U1") (pintype "passive"))
      (node (ref "D20") (pin "C1") (pinfunction "IN2_C1") (pintype "input"))
    )
    (net (code "66") (name "C32H2") (class "Default")
      (node (ref "C52") (pin "H2") (pinfunction "P$1_H2") (pintype "passive"))
      (node (ref "D31") (pin "C1") (pinfunction "IN2_C1") (pintype "input"))
    )
    (net (code "67") (name "DATA0") (class "Default")
      (node (ref "E1") (pin "14") (pinfunction "A3_14") (pintype "output"))
      (node (ref "E9") (pin "14") (pinfunction "D_14") (pintype "input"))
    )
    (net (code "68") (name "DATA00LL") (class "Default")
      (node (ref "A27") (pin "R1") (pinfunction "P$2_R1") (pintype "bidirectional"))
      (node (ref "C46") (pin "A1") (pinfunction "IN1_A1") (pintype "input"))
      (node (ref "D21") (pin "D1") (pinfunction "D_D1") (pintype "open_collector"))
      (node (ref "D22") (pin "D2") (pinfunction "P$1_D2") (pintype "passive"))
    )
    (net (code "69") (name "DATA1") (class "Default")
      (node (ref "E1") (pin "12") (pinfunction "A2_12") (pintype "output"))
      (node (ref "E9") (pin "15") (pinfunction "C_15") (pintype "input"))
    )
    (net (code "70") (name "DATA01L") (class "Default")
      (node (ref "A27") (pin "S1") (pinfunction "P$2_S1") (pintype "bidirectional"))
      (node (ref "C46") (pin "D1") (pinfunction "IN_D1") (pintype "input"))
      (node (ref "D21") (pin "E1") (pinfunction "E_E1") (pintype "open_collector"))
      (node (ref "D22") (pin "E2") (pinfunction "P$1_E2") (pintype "passive"))
    )
    (net (code "71") (name "DATA2") (class "Default")
      (node (ref "E1") (pin "10") (pinfunction "A1_10") (pintype "output"))
      (node (ref "E9") (pin "2") (pinfunction "B_2") (pintype "input"))
    )
    (net (code "72") (name "DATA02L") (class "Default")
      (node (ref "A27") (pin "U1") (pinfunction "P$2_U1") (pintype "bidirectional"))
      (node (ref "C46") (pin "F1") (pinfunction "IN_F1") (pintype "input"))
      (node (ref "D21") (pin "K1") (pinfunction "D_K1") (pintype "open_collector"))
      (node (ref "D22") (pin "F2") (pinfunction "P$1_F2") (pintype "passive"))
    )
    (net (code "73") (name "DATA3") (class "Default")
      (node (ref "E1") (pin "6") (pinfunction "A3_6") (pintype "output"))
      (node (ref "E9") (pin "3") (pinfunction "A_3") (pintype "input"))
    )
    (net (code "74") (name "DATA03L") (class "Default")
      (node (ref "A27") (pin "V1") (pinfunction "P$2_V1") (pintype "bidirectional"))
      (node (ref "C46") (pin "J1") (pinfunction "IN_J1") (pintype "input"))
      (node (ref "D21") (pin "L1") (pinfunction "E_L1") (pintype "open_collector"))
      (node (ref "D22") (pin "H2") (pinfunction "P$1_H2") (pintype "passive"))
    )
    (net (code "75") (name "DATA4") (class "Default")
      (node (ref "E1") (pin "4") (pinfunction "A2_4") (pintype "output"))
      (node (ref "E2") (pin "12") (pinfunction "D_12") (pintype "input"))
      (node (ref "E21") (pin "14") (pinfunction "D_14") (pintype "input"))
    )
    (net (code "76") (name "DATA04L") (class "Default")
      (node (ref "B27") (pin "R1") (pinfunction "P$2_R1") (pintype "bidirectional"))
      (node (ref "C46") (pin "L1") (pinfunction "IN_L1") (pintype "input"))
      (node (ref "D21") (pin "R1") (pinfunction "D_R1") (pintype "open_collector"))
      (node (ref "D22") (pin "J2") (pinfunction "P$1_J2") (pintype "passive"))
    )
    (net (code "77") (name "DATA5") (class "Default")
      (node (ref "E1") (pin "2") (pinfunction "A1_2") (pintype "output"))
      (node (ref "E12") (pin "9") (pinfunction "I0_9") (pintype "input"))
      (node (ref "E2") (pin "2") (pinfunction "D_2") (pintype "input"))
      (node (ref "E21") (pin "15") (pinfunction "C_15") (pintype "input"))
    )
    (net (code "78") (name "DATA05L") (class "Default")
      (node (ref "B27") (pin "S1") (pinfunction "P$2_S1") (pintype "bidirectional"))
      (node (ref "C46") (pin "N1") (pinfunction "IN_N1") (pintype "input"))
      (node (ref "D21") (pin "S1") (pinfunction "E_S1") (pintype "open_collector"))
      (node (ref "D22") (pin "K2") (pinfunction "P$1_K2") (pintype "passive"))
    )
    (net (code "79") (name "DATA6") (class "Default")
      (node (ref "E21") (pin "2") (pinfunction "B_2") (pintype "input"))
      (node (ref "E25") (pin "14") (pinfunction "A3_14") (pintype "output"))
    )
    (net (code "80") (name "DATA06L") (class "Default")
      (node (ref "B27") (pin "U1") (pinfunction "P$2_U1") (pintype "bidirectional"))
      (node (ref "C46") (pin "R1") (pinfunction "IN_R1") (pintype "input"))
      (node (ref "D21") (pin "H2") (pinfunction "D_H2") (pintype "open_collector"))
      (node (ref "D22") (pin "L2") (pinfunction "P$1_L2") (pintype "passive"))
    )
    (net (code "81") (name "DATA7") (class "Default")
      (node (ref "E21") (pin "3") (pinfunction "A_3") (pintype "input"))
      (node (ref "E25") (pin "12") (pinfunction "A2_12") (pintype "output"))
    )
    (net (code "82") (name "DATA07L") (class "Default")
      (node (ref "B27") (pin "V1") (pinfunction "P$2_V1") (pintype "bidirectional"))
      (node (ref "C46") (pin "V1") (pinfunction "IN_V1") (pintype "input"))
      (node (ref "D21") (pin "J2") (pinfunction "E_J2") (pintype "open_collector"))
      (node (ref "D22") (pin "M2") (pinfunction "P$1_M2") (pintype "passive"))
    )
    (net (code "83") (name "DATA8") (class "Default")
      (node (ref "E25") (pin "10") (pinfunction "A1_10") (pintype "output"))
      (node (ref "E33") (pin "14") (pinfunction "D_14") (pintype "input"))
    )
    (net (code "84") (name "DATA08L") (class "Default")
      (node (ref "C46") (pin "E2") (pinfunction "IN_E2") (pintype "input"))
      (node (ref "D21") (pin "N2") (pinfunction "D_N2") (pintype "open_collector"))
      (node (ref "D22") (pin "N2") (pinfunction "P$1_N2") (pintype "passive"))
      (node (ref "D27") (pin "R1") (pinfunction "P$2_R1") (pintype "bidirectional"))
    )
    (net (code "85") (name "DATA9") (class "Default")
      (node (ref "E25") (pin "6") (pinfunction "A3_6") (pintype "output"))
      (node (ref "E33") (pin "15") (pinfunction "C_15") (pintype "input"))
    )
    (net (code "86") (name "DATA09L") (class "Default")
      (node (ref "C46") (pin "H2") (pinfunction "IN_H2") (pintype "input"))
      (node (ref "D21") (pin "P2") (pinfunction "E_P2") (pintype "open_collector"))
      (node (ref "D22") (pin "P2") (pinfunction "P$1_P2") (pintype "passive"))
      (node (ref "D27") (pin "S1") (pinfunction "P$2_S1") (pintype "bidirectional"))
    )
    (net (code "87") (name "DATA10") (class "Default")
      (node (ref "E25") (pin "4") (pinfunction "A2_4") (pintype "output"))
      (node (ref "E33") (pin "2") (pinfunction "B_2") (pintype "input"))
    )
    (net (code "88") (name "DATA10L") (class "Default")
      (node (ref "C46") (pin "K2") (pinfunction "IN_K2") (pintype "input"))
      (node (ref "D21") (pin "U2") (pinfunction "D_U2") (pintype "open_collector"))
      (node (ref "D22") (pin "R2") (pinfunction "P$1_R2") (pintype "passive"))
      (node (ref "D27") (pin "U1") (pinfunction "P$2_U1") (pintype "bidirectional"))
    )
    (net (code "89") (name "DATA11") (class "Default")
      (node (ref "E15") (pin "2") (pinfunction "D_2") (pintype "input"))
      (node (ref "E25") (pin "2") (pinfunction "A1_2") (pintype "output"))
      (node (ref "E33") (pin "3") (pinfunction "A_3") (pintype "input"))
    )
    (net (code "90") (name "DATA11L") (class "Default")
      (node (ref "C46") (pin "M2") (pinfunction "IN_M2") (pintype "input"))
      (node (ref "D21") (pin "V2") (pinfunction "E_V2") (pintype "open_collector"))
      (node (ref "D22") (pin "S2") (pinfunction "P$1_S2") (pintype "passive"))
      (node (ref "D27") (pin "V1") (pinfunction "P$2_V1") (pintype "bidirectional"))
    )
    (net (code "91") (name "DONE") (class "Default")
      (node (ref "E20") (pin "11") (pinfunction "I2_11") (pintype "input"))
      (node (ref "E22") (pin "3") (pinfunction "CLK_3") (pintype "input"))
      (node (ref "E28") (pin "5") (pinfunction "I3_5") (pintype "input"))
      (node (ref "E32") (pin "9") (pinfunction "I_9") (pintype "input"))
      (node (ref "E36") (pin "6") (pinfunction "A3_6") (pintype "output"))
      (node (ref "E39") (pin "11") (pinfunction "I0_11") (pintype "input"))
    )
    (net (code "92") (name "ERROR") (class "Default")
      (node (ref "E26") (pin "3") (pinfunction "CLK_3") (pintype "input"))
      (node (ref "E36") (pin "2") (pinfunction "A1_2") (pintype "output"))
    )
    (net (code "93") (name "GND") (class "Default")
      (node (ref "C1") (pin "2") (pinfunction "2_2") (pintype "passive"))
      (node (ref "C10") (pin "2") (pinfunction "2_2") (pintype "passive"))
      (node (ref "C11") (pin "2") (pinfunction "2_2") (pintype "passive"))
      (node (ref "C12") (pin "2") (pinfunction "2_2") (pintype "passive"))
      (node (ref "C13") (pin "2") (pinfunction "2_2") (pintype "passive"))
      (node (ref "C14") (pin "2") (pinfunction "2_2") (pintype "passive"))
      (node (ref "C15") (pin "2") (pinfunction "2_2") (pintype "passive"))
      (node (ref "C16") (pin "2") (pinfunction "2_2") (pintype "passive"))
      (node (ref "C17") (pin "2") (pinfunction "2_2") (pintype "passive"))
      (node (ref "C18") (pin "2") (pinfunction "2_2") (pintype "passive"))
      (node (ref "C19") (pin "2") (pinfunction "2_2") (pintype "passive"))
      (node (ref "C2") (pin "2") (pinfunction "2_2") (pintype "passive"))
      (node (ref "C20") (pin "2") (pinfunction "2_2") (pintype "passive"))
      (node (ref "C21") (pin "2") (pinfunction "2_2") (pintype "passive"))
      (node (ref "C22") (pin "2") (pinfunction "2_2") (pintype "passive"))
      (node (ref "C23") (pin "2") (pinfunction "2_2") (pintype "passive"))
      (node (ref "C24") (pin "2") (pinfunction "2_2") (pintype "passive"))
      (node (ref "C25") (pin "2") (pinfunction "2_2") (pintype "passive"))
      (node (ref "C26") (pin "2") (pinfunction "2_2") (pintype "passive"))
      (node (ref "C27") (pin "2") (pinfunction "2_2") (pintype "passive"))
      (node (ref "C28") (pin "2") (pinfunction "2_2") (pintype "passive"))
      (node (ref "C29") (pin "2") (pinfunction "2_2") (pintype "passive"))
      (node (ref "C3") (pin "2") (pinfunction "2_2") (pintype "passive"))
      (node (ref "C30") (pin "2") (pinfunction "2_2") (pintype "passive"))
      (node (ref "C31") (pin "2") (pinfunction "2_2") (pintype "passive"))
      (node (ref "C32") (pin "2") (pinfunction "2_2") (pintype "passive"))
      (node (ref "C33") (pin "2") (pinfunction "2_2") (pintype "passive"))
      (node (ref "C34") (pin "2") (pinfunction "2_2") (pintype "passive"))
      (node (ref "C35") (pin "2") (pinfunction "2_2") (pintype "passive"))
      (node (ref "C36") (pin "2") (pinfunction "2_2") (pintype "passive"))
      (node (ref "C37") (pin "2") (pinfunction "2_2") (pintype "passive"))
      (node (ref "C38") (pin "2") (pinfunction "2_2") (pintype "passive"))
      (node (ref "C39") (pin "2") (pinfunction "2_2") (pintype "passive"))
      (node (ref "C4") (pin "2") (pinfunction "2_2") (pintype "passive"))
      (node (ref "C40") (pin "2") (pinfunction "2_2") (pintype "passive"))
      (node (ref "C41") (pin "2") (pinfunction "2_2") (pintype "passive"))
      (node (ref "C42") (pin "-") (pinfunction "-_-") (pintype "passive"))
      (node (ref "C43") (pin "-") (pinfunction "-_-") (pintype "passive"))
      (node (ref "C44") (pin "-") (pinfunction "-_-") (pintype "passive"))
      (node (ref "C45") (pin "-") (pinfunction "-_-") (pintype "passive"))
      (node (ref "C46") (pin "D2") (pinfunction "IN2_D2") (pintype "input"))
      (node (ref "C5") (pin "2") (pinfunction "2_2") (pintype "passive"))
      (node (ref "C6") (pin "2") (pinfunction "2_2") (pintype "passive"))
      (node (ref "C7") (pin "2") (pinfunction "2_2") (pintype "passive"))
      (node (ref "C8") (pin "2") (pinfunction "2_2") (pintype "passive"))
      (node (ref "C9") (pin "2") (pinfunction "2_2") (pintype "passive"))
      (node (ref "DRIVE") (pin "A") (pinfunction "1_A") (pintype "bidirectional"))
      (node (ref "DRIVE") (pin "AA") (pinfunction "23_AA") (pintype "bidirectional"))
      (node (ref "DRIVE") (pin "B") (pinfunction "2_B") (pintype "bidirectional"))
      (node (ref "DRIVE") (pin "C") (pinfunction "3_C") (pintype "bidirectional"))
      (node (ref "DRIVE") (pin "CC") (pinfunction "25_CC") (pintype "bidirectional"))
      (node (ref "DRIVE") (pin "DD") (pinfunction "26_DD") (pintype "bidirectional"))
      (node (ref "DRIVE") (pin "E") (pinfunction "5_E") (pintype "bidirectional"))
      (node (ref "DRIVE") (pin "EE") (pinfunction "27_EE") (pintype "bidirectional"))
      (node (ref "DRIVE") (pin "F") (pinfunction "6_F") (pintype "bidirectional"))
      (node (ref "DRIVE") (pin "H") (pinfunction "7_H") (pintype "bidirectional"))
      (node (ref "DRIVE") (pin "HH") (pinfunction "29_HH") (pintype "bidirectional"))
      (node (ref "DRIVE") (pin "JJ") (pinfunction "30_JJ") (pintype "bidirectional"))
      (node (ref "DRIVE") (pin "K") (pinfunction "9_K") (pintype "bidirectional"))
      (node (ref "DRIVE") (pin "KK") (pinfunction "31_KK") (pintype "bidirectional"))
      (node (ref "DRIVE") (pin "L") (pinfunction "10_L") (pintype "bidirectional"))
      (node (ref "DRIVE") (pin "M") (pinfunction "11_M") (pintype "bidirectional"))
      (node (ref "DRIVE") (pin "MM") (pinfunction "33_MM") (pintype "bidirectional"))
      (node (ref "DRIVE") (pin "NN") (pinfunction "34_NN") (pintype "bidirectional"))
      (node (ref "DRIVE") (pin "P") (pinfunction "13_P") (pintype "bidirectional"))
      (node (ref "DRIVE") (pin "PP") (pinfunction "35_PP") (pintype "bidirectional"))
      (node (ref "DRIVE") (pin "R") (pinfunction "14_R") (pintype "bidirectional"))
      (node (ref "DRIVE") (pin "S") (pinfunction "15_S") (pintype "bidirectional"))
      (node (ref "DRIVE") (pin "SS") (pinfunction "37_SS") (pintype "bidirectional"))
      (node (ref "DRIVE") (pin "TT") (pinfunction "38_TT") (pintype "bidirectional"))
      (node (ref "DRIVE") (pin "U") (pinfunction "17_U") (pintype "bidirectional"))
      (node (ref "DRIVE") (pin "UU") (pinfunction "39_UU") (pintype "bidirectional"))
      (node (ref "DRIVE") (pin "V") (pinfunction "18_V") (pintype "bidirectional"))
      (node (ref "DRIVE") (pin "VV") (pinfunction "40_VV") (pintype "bidirectional"))
      (node (ref "DRIVE") (pin "W") (pinfunction "19_W") (pintype "bidirectional"))
      (node (ref "DRIVE") (pin "Y") (pinfunction "21_Y") (pintype "bidirectional"))
      (node (ref "DRIVE") (pin "Z") (pinfunction "22_Z") (pintype "bidirectional"))
      (node (ref "E11") (pin "10") (pinfunction "I1_10") (pintype "input"))
      (node (ref "E11") (pin "5") (pinfunction "I1_5") (pintype "input"))
      (node (ref "E11") (pin "7") (pinfunction "I1_7") (pintype "input"))
      (node (ref "E39") (pin "7") (pinfunction "I1_7") (pintype "input"))
      (node (ref "E4") (pin "6") (pinfunction "D_6") (pintype "input"))
      (node (ref "R10") (pin "1") (pinfunction "1_1") (pintype "passive"))
      (node (ref "R11") (pin "1") (pinfunction "1_1") (pintype "passive"))
      (node (ref "R12") (pin "1") (pinfunction "1_1") (pintype "passive"))
      (node (ref "R13") (pin "1") (pinfunction "1_1") (pintype "passive"))
      (node (ref "R14") (pin "1") (pinfunction "1_1") (pintype "passive"))
      (node (ref "R15") (pin "1") (pinfunction "1_1") (pintype "passive"))
      (node (ref "R16") (pin "1") (pinfunction "1_1") (pintype "passive"))
      (node (ref "R17") (pin "1") (pinfunction "1_1") (pintype "passive"))
      (node (ref "U$2") (pin "AC2") (pinfunction "1_AC2") (pintype "bidirectional"))
      (node (ref "U$2") (pin "AT1") (pinfunction "1_AT1") (pintype "bidirectional"))
      (node (ref "U$2") (pin "AT2") (pinfunction "1_AT2") (pintype "bidirectional"))
      (node (ref "U$2") (pin "BC2") (pinfunction "1_BC2") (pintype "bidirectional"))
      (node (ref "U$2") (pin "BT1") (pinfunction "1_BT1") (pintype "bidirectional"))
      (node (ref "U$2") (pin "CC2") (pinfunction "1_CC2") (pintype "bidirectional"))
      (node (ref "U$2") (pin "CT1") (pinfunction "1_CT1") (pintype "bidirectional"))
      (node (ref "U$2") (pin "DC2") (pinfunction "1_DC2") (pintype "bidirectional"))
      (node (ref "U$2") (pin "DT1") (pinfunction "1_DT1") (pintype "bidirectional"))
    )
    (net (code "94") (name "INIT") (class "Default")
      (node (ref "E19") (pin "6") (pinfunction "I1_6") (pintype "input"))
      (node (ref "E23") (pin "3") (pinfunction "I1_3") (pintype "input"))
      (node (ref "E23") (pin "6") (pinfunction "I1_6") (pintype "input"))
      (node (ref "E24") (pin "3") (pinfunction "O_3") (pintype "output"))
      (node (ref "E32") (pin "3") (pinfunction "I_3") (pintype "input"))
      (node (ref "E37") (pin "11") (pinfunction "I0_11") (pintype "input"))
      (node (ref "E37") (pin "12") (pinfunction "I1_12") (pintype "input"))
      (node (ref "E6") (pin "12") (pinfunction "I1_12") (pintype "input"))
      (node (ref "E8") (pin "5") (pinfunction "I_5") (pintype "input"))
    )
    (net (code "95") (name "INITIALIZE") (class "Default")
      (node (ref "E11") (pin "6") (pinfunction "I0_6") (pintype "input"))
      (node (ref "U$2") (pin "CR1") (pinfunction "1_CR1") (pintype "bidirectional"))
    )
    (net (code "96") (name "IRQL") (class "Default")
      (node (ref "C46") (pin "S2") (pinfunction "IN_S2") (pintype "input"))
      (node (ref "C48") (pin "P1") (pinfunction "P$2_P1") (pintype "bidirectional"))
      (node (ref "C52") (pin "L2") (pinfunction "P$1_L2") (pintype "passive"))
    )
    (net (code "97") (name "LCD_IOT") (class "Default")
      (node (ref "E12") (pin "10") (pinfunction "I1_10") (pintype "input"))
      (node (ref "E28") (pin "4") (pinfunction "I2_4") (pintype "input"))
      (node (ref "E38") (pin "4") (pinfunction "O_4") (pintype "output"))
    )
    (net (code "98") (name "MAINT") (class "Default")
      (node (ref "E2") (pin "9") (pinfunction "Q_9") (pintype "output"))
      (node (ref "E20") (pin "9") (pinfunction "I0_9") (pintype "input"))
    )
    (net (code "99") (name "MD09L") (class "Default")
      (node (ref "C47") (pin "E1") (pinfunction "OUT_E1") (pintype "open_collector"))
      (node (ref "D27") (pin "L1") (pinfunction "P$2_L1") (pintype "bidirectional"))
    )
    (net (code "100") (name "MD10L") (class "Default")
      (node (ref "C47") (pin "L1") (pinfunction "OUT_L1") (pintype "open_collector"))
      (node (ref "D27") (pin "M1") (pinfunction "P$2_M1") (pintype "bidirectional"))
    )
    (net (code "101") (name "MD11L") (class "Default")
      (node (ref "C47") (pin "S1") (pinfunction "OUT_S1") (pintype "open_collector"))
      (node (ref "D27") (pin "P1") (pinfunction "P$2_P1") (pintype "bidirectional"))
    )
    (net (code "102") (name "MSB8") (class "Default")
      (node (ref "E17") (pin "3") (pinfunction "I1_3") (pintype "input"))
      (node (ref "E21") (pin "11") (pinfunction "QD_11") (pintype "output"))
      (node (ref "E3") (pin "5") (pinfunction "I2_5") (pintype "input"))
      (node (ref "E9") (pin "4") (pinfunction "SER_4") (pintype "input"))
    )
    (net (code "103") (name "MSB12") (class "Default")
      (node (ref "E3") (pin "2") (pinfunction "I1_2") (pintype "input"))
      (node (ref "E5") (pin "3") (pinfunction "I1_3") (pintype "input"))
      (node (ref "E9") (pin "11") (pinfunction "QD_11") (pintype "output"))
    )
    (net (code "104") (name "Net-(C46Q-IN)") (class "Default")
      (node (ref "C46") (pin "U2") (pinfunction "IN_U2") (pintype "input"))
      (node (ref "C49") (pin "F2") (pinfunction "OUT_F2") (pintype "output"))
    )
    (net (code "105") (name "Net-(C47F-IN1)") (class "Default")
      (node (ref "C47") (pin "K2") (pinfunction "IN1_K2") (pintype "input"))
      (node (ref "C47") (pin "M2") (pinfunction "IN3_M2") (pintype "input"))
      (node (ref "C49") (pin "C1") (pinfunction "OUT_C1") (pintype "output"))
    )
    (net (code "106") (name "Net-(C49B-OUT)") (class "Default")
      (node (ref "C49") (pin "E2") (pinfunction "IN2_E2") (pintype "input"))
      (node (ref "C49") (pin "F1") (pinfunction "OUT_F1") (pintype "output"))
    )
    (net (code "107") (name "Net-(C49C-IN1)") (class "Default")
      (node (ref "C49") (pin "D2") (pinfunction "IN1_D2") (pintype "input"))
      (node (ref "C49") (pin "K1") (pinfunction "OUT_K1") (pintype "output"))
    )
    (net (code "108") (name "Net-(C50A-IN1)") (class "Default")
      (node (ref "C50") (pin "A1") (pinfunction "IN1_A1") (pintype "input"))
      (node (ref "C50") (pin "K1") (pinfunction "OUT_K1") (pintype "output"))
    )
    (net (code "109") (name "Net-(C50A-IN2)") (class "Default")
      (node (ref "C50") (pin "B1") (pinfunction "IN2_B1") (pintype "input"))
      (node (ref "C50") (pin "D2") (pinfunction "IN1_D2") (pintype "input"))
      (node (ref "C50") (pin "F1") (pinfunction "OUT_F1") (pintype "output"))
    )
    (net (code "110") (name "Net-(C50A-OUT)") (class "Default")
      (node (ref "C50") (pin "C1") (pinfunction "OUT_C1") (pintype "output"))
      (node (ref "C50") (pin "D1") (pinfunction "IN1_D1") (pintype "input"))
    )
    (net (code "111") (name "Net-(C50B-IN2)") (class "Default")
      (node (ref "C50") (pin "E1") (pinfunction "IN2_E1") (pintype "input"))
      (node (ref "C50") (pin "K2") (pinfunction "OUT_K2") (pintype "output"))
    )
    (net (code "112") (name "Net-(C50C-IN2)") (class "Default")
      (node (ref "C50") (pin "E2") (pinfunction "IN2_E2") (pintype "input"))
      (node (ref "C50") (pin "J1") (pinfunction "IN2_J1") (pintype "input"))
      (node (ref "C50") (pin "J2") (pinfunction "IN2_J2") (pintype "input"))
      (node (ref "D31") (pin "K1") (pinfunction "OUT_K1") (pintype "output"))
    )
    (net (code "113") (name "Net-(C50F-IN1)") (class "Default")
      (node (ref "C50") (pin "H1") (pinfunction "IN1_H1") (pintype "input"))
      (node (ref "C50") (pin "N2") (pinfunction "OUT_N2") (pintype "output"))
    )
    (net (code "114") (name "Net-(C50G-IN1)") (class "Default")
      (node (ref "C50") (pin "H2") (pinfunction "IN1_H2") (pintype "input"))
      (node (ref "C51") (pin "F1") (pinfunction "OUT_F1") (pintype "output"))
    )
    (net (code "115") (name "Net-(C50H-OUT)") (class "Default")
      (node (ref "C50") (pin "L2") (pinfunction "IN1_L2") (pintype "input"))
      (node (ref "C50") (pin "M2") (pinfunction "IN2_M2") (pintype "input"))
      (node (ref "C50") (pin "N1") (pinfunction "OUT_N1") (pintype "output"))
    )
    (net (code "116") (name "Net-(C51A-IN)") (class "Default")
      (node (ref "C51") (pin "E1") (pinfunction "IN_E1") (pintype "input"))
      (node (ref "C51") (pin "T2") (pinfunction "T2_T2") (pintype "output"))
    )
    (net (code "117") (name "Net-(C52A-P$1)") (class "Default")
      (node (ref "C52") (pin "D2") (pinfunction "P$1_D2") (pintype "passive"))
      (node (ref "D31") (pin "A1") (pinfunction "IN1_A1") (pintype "input"))
      (node (ref "D32") (pin "D2") (pinfunction "P$2_D2") (pintype "bidirectional"))
    )
    (net (code "118") (name "Net-(C52B-P$1)") (class "Default")
      (node (ref "C52") (pin "E2") (pinfunction "P$1_E2") (pintype "passive"))
      (node (ref "D31") (pin "D1") (pinfunction "IN_D1") (pintype "input"))
      (node (ref "D32") (pin "E2") (pinfunction "P$2_E2") (pintype "bidirectional"))
    )
    (net (code "119") (name "Net-(C52C-P$1)") (class "Default")
      (node (ref "C52") (pin "F2") (pinfunction "P$1_F2") (pintype "passive"))
      (node (ref "D31") (pin "F1") (pinfunction "IN_F1") (pintype "input"))
      (node (ref "D32") (pin "H2") (pinfunction "P$2_H2") (pintype "bidirectional"))
    )
    (net (code "120") (name "Net-(C52J-P$1)") (class "Default")
      (node (ref "C52") (pin "N2") (pinfunction "P$1_N2") (pintype "passive"))
      (node (ref "D31") (pin "L1") (pinfunction "IN_L1") (pintype "input"))
      (node (ref "D32") (pin "K2") (pinfunction "P$2_K2") (pintype "bidirectional"))
    )
    (net (code "121") (name "Net-(D20A-OUT)") (class "Default")
      (node (ref "D20") (pin "B1") (pinfunction "OUT_B1") (pintype "output"))
      (node (ref "D21") (pin "A1") (pinfunction "A_A1") (pintype "input"))
    )
    (net (code "122") (name "Net-(D20B-OUT)") (class "Default")
      (node (ref "D20") (pin "E1") (pinfunction "OUT_E1") (pintype "output"))
      (node (ref "D21") (pin "B1") (pinfunction "B_B1") (pintype "input"))
    )
    (net (code "123") (name "Net-(D20C-OUT)") (class "Default")
      (node (ref "D20") (pin "F2") (pinfunction "OUT_F2") (pintype "output"))
      (node (ref "D21") (pin "K2") (pinfunction "A_K2") (pintype "input"))
    )
    (net (code "124") (name "Net-(D20F-OUT)") (class "Default")
      (node (ref "D20") (pin "H1") (pinfunction "OUT_H1") (pintype "output"))
      (node (ref "D21") (pin "F1") (pinfunction "A_F1") (pintype "input"))
    )
    (net (code "125") (name "Net-(D20G-OUT)") (class "Default")
      (node (ref "D20") (pin "J2") (pinfunction "OUT_J2") (pintype "output"))
      (node (ref "D21") (pin "L2") (pinfunction "B_L2") (pintype "input"))
    )
    (net (code "126") (name "Net-(D20H-OUT)") (class "Default")
      (node (ref "D20") (pin "K1") (pinfunction "OUT_K1") (pintype "output"))
      (node (ref "D21") (pin "H1") (pinfunction "B_H1") (pintype "input"))
    )
    (net (code "127") (name "Net-(D20I-OUT)") (class "Default")
      (node (ref "D20") (pin "L2") (pinfunction "OUT_L2") (pintype "output"))
      (node (ref "D21") (pin "R2") (pinfunction "A_R2") (pintype "input"))
    )
    (net (code "128") (name "Net-(D20J-OUT)") (class "Default")
      (node (ref "D20") (pin "M1") (pinfunction "OUT_M1") (pintype "output"))
      (node (ref "D21") (pin "M1") (pinfunction "A_M1") (pintype "input"))
    )
    (net (code "129") (name "Net-(D20K-OUT)") (class "Default")
      (node (ref "D20") (pin "N2") (pinfunction "OUT_N2") (pintype "output"))
      (node (ref "D21") (pin "S2") (pinfunction "B_S2") (pintype "input"))
    )
    (net (code "130") (name "Net-(D20L-OUT)") (class "Default")
      (node (ref "D20") (pin "P1") (pinfunction "OUT_P1") (pintype "output"))
      (node (ref "D21") (pin "N1") (pinfunction "B_N1") (pintype "input"))
    )
    (net (code "131") (name "Net-(D20N-OUT)") (class "Default")
      (node (ref "D20") (pin "S1") (pinfunction "OUT_S1") (pintype "output"))
      (node (ref "D21") (pin "D2") (pinfunction "A_D2") (pintype "input"))
    )
    (net (code "132") (name "Net-(D20P-OUT)") (class "Default")
      (node (ref "D20") (pin "U1") (pinfunction "OUT_U1") (pintype "output"))
      (node (ref "D21") (pin "E2") (pinfunction "B_E2") (pintype "input"))
    )
    (net (code "133") (name "Net-(E2A-CLK)") (class "Default")
      (node (ref "E2") (pin "11") (pinfunction "CLK_11") (pintype "input"))
      (node (ref "E2") (pin "3") (pinfunction "CLK_3") (pintype "input"))
      (node (ref "E6") (pin "1") (pinfunction "O_1") (pintype "output"))
    )
    (net (code "134") (name "Net-(E3A-I2)") (class "Default")
      (node (ref "E3") (pin "13") (pinfunction "I2_13") (pintype "input"))
      (node (ref "E3") (pin "3") (pinfunction "I0_3") (pintype "input"))
      (node (ref "E8") (pin "2") (pinfunction "O_2") (pintype "output"))
    )
    (net (code "135") (name "Net-(E3A-O)") (class "Default")
      (node (ref "E3") (pin "11") (pinfunction "I2_11") (pintype "input"))
      (node (ref "E3") (pin "12") (pinfunction "O_12") (pintype "output"))
    )
    (net (code "136") (name "Net-(E3B-O)") (class "Default")
      (node (ref "E3") (pin "6") (pinfunction "O_6") (pintype "output"))
      (node (ref "E3") (pin "9") (pinfunction "I0_9") (pintype "input"))
    )
    (net (code "137") (name "Net-(E4A-CLK)") (class "Default")
      (node (ref "E4") (pin "2") (pinfunction "CLK_2") (pintype "input"))
      (node (ref "E8") (pin "13") (pinfunction "I_13") (pintype "input"))
      (node (ref "E8") (pin "4") (pinfunction "O_4") (pintype "output"))
    )
    (net (code "138") (name "Net-(E5B-I1)") (class "Default")
      (node (ref "E5") (pin "6") (pinfunction "I1_6") (pintype "input"))
      (node (ref "E9") (pin "9") (pinfunction "QC_9") (pintype "output"))
    )
    (net (code "139") (name "Net-(E5C-I1)") (class "Default")
      (node (ref "E5") (pin "9") (pinfunction "I1_9") (pintype "input"))
      (node (ref "E9") (pin "7") (pinfunction "QB_7") (pintype "output"))
    )
    (net (code "140") (name "Net-(E5D-I1)") (class "Default")
      (node (ref "E5") (pin "12") (pinfunction "I1_12") (pintype "input"))
      (node (ref "E9") (pin "5") (pinfunction "QA_5") (pintype "output"))
    )
    (net (code "141") (name "Net-(E10A-I1)") (class "Default")
      (node (ref "E10") (pin "2") (pinfunction "I1_2") (pintype "input"))
      (node (ref "E10") (pin "6") (pinfunction "O_6") (pintype "output"))
      (node (ref "E14") (pin "12") (pinfunction "I1_12") (pintype "input"))
    )
    (net (code "142") (name "Net-(E10A-O)") (class "Default")
      (node (ref "E10") (pin "12") (pinfunction "O_12") (pintype "output"))
      (node (ref "E12") (pin "5") (pinfunction "I1_5") (pintype "input"))
    )
    (net (code "143") (name "Net-(E10C-O)") (class "Default")
      (node (ref "E10") (pin "8") (pinfunction "O_8") (pintype "output"))
      (node (ref "E18") (pin "8") (pinfunction "I0_8") (pintype "input"))
      (node (ref "E18") (pin "9") (pinfunction "I1_9") (pintype "input"))
    )
    (net (code "144") (name "Net-(E11A-O)") (class "Default")
      (node (ref "E11") (pin "3") (pinfunction "O_3") (pintype "output"))
      (node (ref "E7") (pin "4") (pinfunction "PRE_4") (pintype "input"))
      (node (ref "E8") (pin "9") (pinfunction "I_9") (pintype "input"))
    )
    (net (code "145") (name "Net-(E11B-O)") (class "Default")
      (node (ref "E11") (pin "2") (pinfunction "O_2") (pintype "output"))
      (node (ref "E24") (pin "1") (pinfunction "I0_1") (pintype "input"))
    )
    (net (code "146") (name "Net-(E12A-I0)") (class "Default")
      (node (ref "E12") (pin "1") (pinfunction "I0_1") (pintype "input"))
      (node (ref "E12") (pin "11") (pinfunction "O_11") (pintype "output"))
    )
    (net (code "147") (name "Net-(E12A-I1)") (class "Default")
      (node (ref "E12") (pin "2") (pinfunction "I1_2") (pintype "input"))
      (node (ref "E12") (pin "8") (pinfunction "O_8") (pintype "output"))
    )
    (net (code "148") (name "Net-(E12A-O)") (class "Default")
      (node (ref "E12") (pin "3") (pinfunction "O_3") (pintype "output"))
      (node (ref "E4") (pin "5") (pinfunction "C_5") (pintype "input"))
    )
    (net (code "149") (name "Net-(E12B-O)") (class "Default")
      (node (ref "E12") (pin "6") (pinfunction "O_6") (pintype "output"))
      (node (ref "E14") (pin "2") (pinfunction "I0_2") (pintype "input"))
      (node (ref "E14") (pin "3") (pinfunction "I1_3") (pintype "input"))
    )
    (net (code "150") (name "Net-(E14B-I1)") (class "Default")
      (node (ref "E14") (pin "6") (pinfunction "I1_6") (pintype "input"))
      (node (ref "E27") (pin "16") (pinfunction "K_16") (pintype "input"))
      (node (ref "E27") (pin "4") (pinfunction "J_4") (pintype "input"))
      (node (ref "E3") (pin "8") (pinfunction "O_8") (pintype "output"))
    )
    (net (code "151") (name "Net-(E15A-CLK)") (class "Default")
      (node (ref "E15") (pin "3") (pinfunction "CLK_3") (pintype "input"))
      (node (ref "E6") (pin "4") (pinfunction "O_4") (pintype "output"))
    )
    (net (code "152") (name "Net-(E15A-Q)") (class "Default")
      (node (ref "E15") (pin "5") (pinfunction "Q_5") (pintype "output"))
      (node (ref "E18") (pin "5") (pinfunction "I0_5") (pintype "input"))
    )
    (net (code "153") (name "Net-(E15B-CLK)") (class "Default")
      (node (ref "E15") (pin "11") (pinfunction "CLK_11") (pintype "input"))
      (node (ref "E24") (pin "6") (pinfunction "O_6") (pintype "output"))
    )
    (net (code "154") (name "Net-(E15B-CLR)") (class "Default")
      (node (ref "E15") (pin "13") (pinfunction "CLR_13") (pintype "input"))
      (node (ref "E16") (pin "8") (pinfunction "O_8") (pintype "output"))
    )
    (net (code "155") (name "Net-(E16A-I1)") (class "Default")
      (node (ref "E16") (pin "2") (pinfunction "I1_2") (pintype "input"))
      (node (ref "E17") (pin "11") (pinfunction "I0_11") (pintype "input"))
      (node (ref "E17") (pin "2") (pinfunction "I0_2") (pintype "input"))
      (node (ref "E17") (pin "5") (pinfunction "I0_5") (pintype "input"))
      (node (ref "E17") (pin "8") (pinfunction "I0_8") (pintype "input"))
      (node (ref "E19") (pin "13") (pinfunction "O_13") (pintype "output"))
      (node (ref "E29") (pin "11") (pinfunction "I0_11") (pintype "input"))
      (node (ref "E29") (pin "2") (pinfunction "I0_2") (pintype "input"))
      (node (ref "E29") (pin "5") (pinfunction "I0_5") (pintype "input"))
      (node (ref "E29") (pin "8") (pinfunction "I0_8") (pintype "input"))
    )
    (net (code "156") (name "Net-(E16A-O)") (class "Default")
      (node (ref "E16") (pin "3") (pinfunction "O_3") (pintype "output"))
      (node (ref "E5") (pin "11") (pinfunction "I0_11") (pintype "input"))
      (node (ref "E5") (pin "2") (pinfunction "I0_2") (pintype "input"))
      (node (ref "E5") (pin "5") (pinfunction "I0_5") (pintype "input"))
      (node (ref "E5") (pin "8") (pinfunction "I0_8") (pintype "input"))
    )
    (net (code "157") (name "Net-(E16B-O)") (class "Default")
      (node (ref "E16") (pin "6") (pinfunction "O_6") (pintype "output"))
      (node (ref "E20") (pin "2") (pinfunction "I1_2") (pintype "input"))
    )
    (net (code "158") (name "Net-(E16C-I0)") (class "Default")
      (node (ref "E16") (pin "9") (pinfunction "I0_9") (pintype "input"))
      (node (ref "E24") (pin "9") (pinfunction "I0_9") (pintype "input"))
      (node (ref "E39") (pin "13") (pinfunction "O_13") (pintype "output"))
    )
    (net (code "159") (name "Net-(E16D-I1)") (class "Default")
      (node (ref "E16") (pin "13") (pinfunction "I1_13") (pintype "input"))
      (node (ref "E24") (pin "8") (pinfunction "O_8") (pintype "output"))
    )
    (net (code "160") (name "Net-(E17B-I1)") (class "Default")
      (node (ref "E17") (pin "6") (pinfunction "I1_6") (pintype "input"))
      (node (ref "E21") (pin "9") (pinfunction "QC_9") (pintype "output"))
    )
    (net (code "161") (name "Net-(E17C-I1)") (class "Default")
      (node (ref "E17") (pin "9") (pinfunction "I1_9") (pintype "input"))
      (node (ref "E21") (pin "7") (pinfunction "QB_7") (pintype "output"))
    )
    (net (code "162") (name "Net-(E17D-I1)") (class "Default")
      (node (ref "E17") (pin "12") (pinfunction "I1_12") (pintype "input"))
      (node (ref "E21") (pin "5") (pinfunction "QA_5") (pintype "output"))
    )
    (net (code "163") (name "Net-(E18A-I0)") (class "Default")
      (node (ref "E18") (pin "2") (pinfunction "I0_2") (pintype "input"))
      (node (ref "E18") (pin "3") (pinfunction "I1_3") (pintype "input"))
      (node (ref "E32") (pin "5") (pinfunction "I_5") (pintype "input"))
      (node (ref "E35") (pin "3") (pinfunction "O_3") (pintype "output"))
      (node (ref "E38") (pin "1") (pinfunction "I_1") (pintype "input"))
    )
    (net (code "164") (name "Net-(E18B-I1)") (class "Default")
      (node (ref "E18") (pin "6") (pinfunction "I1_6") (pintype "input"))
      (node (ref "E22") (pin "9") (pinfunction "Q_9") (pintype "output"))
      (node (ref "E34") (pin "13") (pinfunction "I1_13") (pintype "input"))
    )
    (net (code "165") (name "Net-(E19A-I0)") (class "Default")
      (node (ref "E19") (pin "2") (pinfunction "I0_2") (pintype "input"))
      (node (ref "E20") (pin "12") (pinfunction "O_12") (pintype "output"))
    )
    (net (code "166") (name "Net-(E19B-I0)") (class "Default")
      (node (ref "E19") (pin "10") (pinfunction "O_10") (pintype "output"))
      (node (ref "E19") (pin "5") (pinfunction "I0_5") (pintype "input"))
    )
    (net (code "167") (name "Net-(E19B-O)") (class "Default")
      (node (ref "E19") (pin "4") (pinfunction "O_4") (pintype "output"))
      (node (ref "E22") (pin "1") (pinfunction "CLR_1") (pintype "input"))
    )
    (net (code "168") (name "Net-(E19D-I0)") (class "Default")
      (node (ref "E19") (pin "11") (pinfunction "I0_11") (pintype "input"))
      (node (ref "E20") (pin "8") (pinfunction "O_8") (pintype "output"))
    )
    (net (code "169") (name "Net-(E21A-SER)") (class "Default")
      (node (ref "E21") (pin "4") (pinfunction "SER_4") (pintype "input"))
      (node (ref "E29") (pin "3") (pinfunction "I1_3") (pintype "input"))
      (node (ref "E33") (pin "11") (pinfunction "QD_11") (pintype "output"))
    )
    (net (code "170") (name "Net-(E22A-Q)") (class "Default")
      (node (ref "E22") (pin "12") (pinfunction "D_12") (pintype "input"))
      (node (ref "E22") (pin "5") (pinfunction "Q_5") (pintype "output"))
    )
    (net (code "171") (name "Net-(E23A-I0)") (class "Default")
      (node (ref "E23") (pin "13") (pinfunction "O_13") (pintype "output"))
      (node (ref "E23") (pin "2") (pinfunction "I0_2") (pintype "input"))
    )
    (net (code "172") (name "Net-(E23A-O)") (class "Default")
      (node (ref "E23") (pin "1") (pinfunction "O_1") (pintype "output"))
      (node (ref "E30") (pin "1") (pinfunction "CLR_1") (pintype "input"))
    )
    (net (code "173") (name "Net-(E23B-I0)") (class "Default")
      (node (ref "E23") (pin "10") (pinfunction "O_10") (pintype "output"))
      (node (ref "E23") (pin "5") (pinfunction "I0_5") (pintype "input"))
    )
    (net (code "174") (name "Net-(E23B-O)") (class "Default")
      (node (ref "E23") (pin "4") (pinfunction "O_4") (pintype "output"))
      (node (ref "E26") (pin "1") (pinfunction "CLR_1") (pintype "input"))
    )
    (net (code "175") (name "Net-(E24A-I1)") (class "Default")
      (node (ref "E24") (pin "2") (pinfunction "I1_2") (pintype "input"))
      (node (ref "E7") (pin "5") (pinfunction "Q_5") (pintype "output"))
    )
    (net (code "176") (name "Net-(E24B-I0)") (class "Default")
      (node (ref "E24") (pin "4") (pinfunction "I0_4") (pintype "input"))
      (node (ref "E28") (pin "8") (pinfunction "O_8") (pintype "output"))
    )
    (net (code "177") (name "Net-(E24B-I1)") (class "Default")
      (node (ref "E24") (pin "5") (pinfunction "I1_5") (pintype "input"))
      (node (ref "E28") (pin "6") (pinfunction "O_6") (pintype "output"))
    )
    (net (code "178") (name "Net-(E24D-O)") (class "Default")
      (node (ref "E24") (pin "11") (pinfunction "O_11") (pintype "output"))
      (node (ref "E3") (pin "10") (pinfunction "I1_10") (pintype "input"))
    )
    (net (code "179") (name "Net-(E26A-Q)") (class "Default")
      (node (ref "E26") (pin "12") (pinfunction "D_12") (pintype "input"))
      (node (ref "E26") (pin "5") (pinfunction "Q_5") (pintype "output"))
    )
    (net (code "180") (name "Net-(E26B-Q)") (class "Default")
      (node (ref "E26") (pin "9") (pinfunction "Q_9") (pintype "output"))
      (node (ref "E34") (pin "1") (pinfunction "I0_1") (pintype "input"))
    )
    (net (code "181") (name "Net-(E27A-CLR)") (class "Default")
      (node (ref "E27") (pin "3") (pinfunction "CLR_3") (pintype "input"))
      (node (ref "E6") (pin "13") (pinfunction "O_13") (pintype "output"))
    )
    (net (code "182") (name "Net-(E29B-I1)") (class "Default")
      (node (ref "E29") (pin "6") (pinfunction "I1_6") (pintype "input"))
      (node (ref "E33") (pin "9") (pinfunction "QC_9") (pintype "output"))
    )
    (net (code "183") (name "Net-(E29C-I1)") (class "Default")
      (node (ref "E29") (pin "9") (pinfunction "I1_9") (pintype "input"))
      (node (ref "E33") (pin "7") (pinfunction "QB_7") (pintype "output"))
    )
    (net (code "184") (name "Net-(E29D-I1)") (class "Default")
      (node (ref "E29") (pin "12") (pinfunction "I1_12") (pintype "input"))
      (node (ref "E33") (pin "5") (pinfunction "QA_5") (pintype "output"))
    )
    (net (code "185") (name "Net-(E30A-Q)") (class "Default")
      (node (ref "E30") (pin "12") (pinfunction "D_12") (pintype "input"))
      (node (ref "E30") (pin "5") (pinfunction "Q_5") (pintype "output"))
    )
    (net (code "186") (name "Net-(E30B-Q)") (class "Default")
      (node (ref "E30") (pin "9") (pinfunction "Q_9") (pintype "output"))
      (node (ref "E34") (pin "10") (pinfunction "I1_10") (pintype "input"))
    )
    (net (code "187") (name "Net-(E34A-I1)") (class "Default")
      (node (ref "E34") (pin "2") (pinfunction "I1_2") (pintype "input"))
      (node (ref "E38") (pin "8") (pinfunction "O_8") (pintype "output"))
    )
    (net (code "188") (name "Net-(E34C-I0)") (class "Default")
      (node (ref "E34") (pin "9") (pinfunction "I0_9") (pintype "input"))
      (node (ref "E38") (pin "12") (pinfunction "O_12") (pintype "output"))
    )
    (net (code "189") (name "Net-(E34D-I0)") (class "Default")
      (node (ref "E34") (pin "12") (pinfunction "I0_12") (pintype "input"))
      (node (ref "E38") (pin "10") (pinfunction "O_10") (pintype "output"))
    )
    (net (code "190") (name "Net-(E35A-I3)") (class "Default")
      (node (ref "E35") (pin "9") (pinfunction "I3_9") (pintype "input"))
      (node (ref "E39") (pin "2") (pinfunction "O_2") (pintype "output"))
      (node (ref "E40") (pin "7") (pinfunction "FORCE0_7") (pintype "input"))
    )
    (net (code "191") (name "Net-(E35A-I4)") (class "Default")
      (node (ref "E31") (pin "11") (pinfunction "11_11") (pintype "passive"))
      (node (ref "E31") (pin "14") (pinfunction "14_14") (pintype "passive"))
      (node (ref "E35") (pin "10") (pinfunction "I4_10") (pintype "input"))
    )
    (net (code "192") (name "Net-(E35A-I5)") (class "Default")
      (node (ref "E31") (pin "12") (pinfunction "12_12") (pintype "passive"))
      (node (ref "E31") (pin "15") (pinfunction "15_15") (pintype "passive"))
      (node (ref "E35") (pin "11") (pinfunction "I5_11") (pintype "input"))
    )
    (net (code "193") (name "Net-(E35A-I6)") (class "Default")
      (node (ref "E31") (pin "13") (pinfunction "13_13") (pintype "passive"))
      (node (ref "E31") (pin "16") (pinfunction "16_16") (pintype "passive"))
      (node (ref "E35") (pin "12") (pinfunction "I6_12") (pintype "input"))
    )
    (net (code "194") (name "Net-(E38A-O)") (class "Default")
      (node (ref "E38") (pin "2") (pinfunction "O_2") (pintype "output"))
      (node (ref "E40") (pin "9") (pinfunction "FORCE0_9") (pintype "input"))
      (node (ref "E41") (pin "12") (pinfunction "D_12") (pintype "input"))
    )
    (net (code "195") (name "Net-(E40A-A1)") (class "Default")
      (node (ref "E31") (pin "1") (pinfunction "1_1") (pintype "passive"))
      (node (ref "E40") (pin "2") (pinfunction "A1_2") (pintype "output"))
    )
    (net (code "196") (name "Net-(E40A-A2)") (class "Default")
      (node (ref "E31") (pin "2") (pinfunction "2_2") (pintype "passive"))
      (node (ref "E40") (pin "4") (pinfunction "A2_4") (pintype "output"))
    )
    (net (code "197") (name "Net-(E40A-A3)") (class "Default")
      (node (ref "E31") (pin "3") (pinfunction "3_3") (pintype "passive"))
      (node (ref "E40") (pin "6") (pinfunction "A3_6") (pintype "output"))
    )
    (net (code "198") (name "Net-(E40B-A1)") (class "Default")
      (node (ref "E40") (pin "10") (pinfunction "A1_10") (pintype "output"))
      (node (ref "E41") (pin "15") (pinfunction "A_15") (pintype "input"))
    )
    (net (code "199") (name "Net-(E40B-A2)") (class "Default")
      (node (ref "E40") (pin "12") (pinfunction "A2_12") (pintype "output"))
      (node (ref "E41") (pin "14") (pinfunction "B_14") (pintype "input"))
    )
    (net (code "200") (name "Net-(E40B-A3)") (class "Default")
      (node (ref "E40") (pin "14") (pinfunction "A3_14") (pintype "output"))
      (node (ref "E41") (pin "13") (pinfunction "C_13") (pintype "input"))
    )
    (net (code "201") (name "Net-(PAD10-P)") (class "Default")
      (node (ref "E13") (pin "1") (pinfunction "1_1") (pintype "passive"))
      (node (ref "PAD10") (pin "1") (pinfunction "P_1") (pintype "passive"))
    )
    (net (code "202") (name "Net-(PAD11-P)") (class "Default")
      (node (ref "E13") (pin "2") (pinfunction "2_2") (pintype "passive"))
      (node (ref "PAD11") (pin "1") (pinfunction "P_1") (pintype "passive"))
    )
    (net (code "203") (name "Net-(PAD12-P)") (class "Default")
      (node (ref "E13") (pin "3") (pinfunction "3_3") (pintype "passive"))
      (node (ref "PAD12") (pin "1") (pinfunction "P_1") (pintype "passive"))
    )
    (net (code "204") (name "Net-(PAD13-P)") (class "Default")
      (node (ref "E13") (pin "4") (pinfunction "4_4") (pintype "passive"))
      (node (ref "PAD13") (pin "1") (pinfunction "P_1") (pintype "passive"))
    )
    (net (code "205") (name "Net-(PAD14-P)") (class "Default")
      (node (ref "E13") (pin "5") (pinfunction "5_5") (pintype "passive"))
      (node (ref "PAD14") (pin "1") (pinfunction "P_1") (pintype "passive"))
    )
    (net (code "206") (name "Net-(PAD15-P)") (class "Default")
      (node (ref "E13") (pin "6") (pinfunction "6_6") (pintype "passive"))
      (node (ref "PAD15") (pin "1") (pinfunction "P_1") (pintype "passive"))
    )
    (net (code "207") (name "Net-(PAD16-P)") (class "Default")
      (node (ref "E13") (pin "7") (pinfunction "7_7") (pintype "passive"))
      (node (ref "PAD16") (pin "1") (pinfunction "P_1") (pintype "passive"))
    )
    (net (code "208") (name "Net-(PAD17-P)") (class "Default")
      (node (ref "E13") (pin "8") (pinfunction "8_8") (pintype "passive"))
      (node (ref "PAD17") (pin "1") (pinfunction "P_1") (pintype "passive"))
    )
    (net (code "209") (name "Net-(PAD20-P)") (class "Default")
      (node (ref "E13") (pin "16") (pinfunction "16_16") (pintype "passive"))
      (node (ref "PAD20") (pin "1") (pinfunction "P_1") (pintype "passive"))
    )
    (net (code "210") (name "Net-(PAD21-P)") (class "Default")
      (node (ref "E13") (pin "15") (pinfunction "15_15") (pintype "passive"))
      (node (ref "PAD21") (pin "1") (pinfunction "P_1") (pintype "passive"))
    )
    (net (code "211") (name "Net-(PAD22-P)") (class "Default")
      (node (ref "E13") (pin "14") (pinfunction "14_14") (pintype "passive"))
      (node (ref "PAD22") (pin "1") (pinfunction "P_1") (pintype "passive"))
    )
    (net (code "212") (name "Net-(PAD23-P)") (class "Default")
      (node (ref "E13") (pin "13") (pinfunction "13_13") (pintype "passive"))
      (node (ref "PAD23") (pin "1") (pinfunction "P_1") (pintype "passive"))
    )
    (net (code "213") (name "Net-(PAD24-P)") (class "Default")
      (node (ref "E13") (pin "12") (pinfunction "12_12") (pintype "passive"))
      (node (ref "PAD24") (pin "1") (pinfunction "P_1") (pintype "passive"))
    )
    (net (code "214") (name "Net-(PAD25-P)") (class "Default")
      (node (ref "E13") (pin "11") (pinfunction "11_11") (pintype "passive"))
      (node (ref "PAD25") (pin "1") (pinfunction "P_1") (pintype "passive"))
    )
    (net (code "215") (name "Net-(PAD26-P)") (class "Default")
      (node (ref "E13") (pin "10") (pinfunction "10_10") (pintype "passive"))
      (node (ref "PAD26") (pin "1") (pinfunction "P_1") (pintype "passive"))
    )
    (net (code "216") (name "Net-(PAD27-P)") (class "Default")
      (node (ref "E13") (pin "9") (pinfunction "9_9") (pintype "passive"))
      (node (ref "PAD27") (pin "1") (pinfunction "P_1") (pintype "passive"))
    )
    (net (code "217") (name "OPAUSEL") (class "Default")
      (node (ref "C48") (pin "D1") (pinfunction "P$2_D1") (pintype "bidirectional"))
      (node (ref "C50") (pin "F2") (pinfunction "OUT_F2") (pintype "output"))
    )
    (net (code "218") (name "PARITY") (class "Default")
      (node (ref "E24") (pin "13") (pinfunction "I1_13") (pintype "input"))
      (node (ref "E4") (pin "15") (pinfunction "RCO_15") (pintype "output"))
      (node (ref "E8") (pin "1") (pinfunction "I_1") (pintype "input"))
      (node (ref "U$2") (pin "AB1") (pinfunction "1_AB1") (pintype "bidirectional"))
    )
    (net (code "219") (name "PAUSEL") (class "Default")
      (node (ref "C49") (pin "H1") (pinfunction "IN1_H1") (pintype "input"))
      (node (ref "C49") (pin "J1") (pinfunction "IN2_J1") (pintype "input"))
      (node (ref "D31") (pin "H1") (pinfunction "OUT_H1") (pintype "output"))
      (node (ref "D31") (pin "J1") (pinfunction "IN_J1") (pintype "input"))
    )
    (net (code "220") (name "POWEROK") (class "Default")
      (node (ref "B27") (pin "V2") (pinfunction "P$2_V2") (pintype "bidirectional"))
      (node (ref "C52") (pin "M2") (pinfunction "P$1_M2") (pintype "passive"))
    )
    (net (code "221") (name "RD") (class "Default")
      (node (ref "E20") (pin "10") (pinfunction "I1_10") (pintype "input"))
      (node (ref "E32") (pin "1") (pinfunction "I_1") (pintype "input"))
      (node (ref "E36") (pin "14") (pinfunction "A3_14") (pintype "output"))
    )
    (net (code "222") (name "RUN") (class "Default")
      (node (ref "E15") (pin "9") (pinfunction "Q_9") (pintype "output"))
      (node (ref "E18") (pin "11") (pinfunction "I0_11") (pintype "input"))
      (node (ref "E18") (pin "12") (pinfunction "I1_12") (pintype "input"))
      (node (ref "E6") (pin "11") (pinfunction "I0_11") (pintype "input"))
    )
    (net (code "223") (name "RX_DATA") (class "Default")
      (node (ref "E33") (pin "4") (pinfunction "SER_4") (pintype "input"))
      (node (ref "E36") (pin "10") (pinfunction "A1_10") (pintype "output"))
    )
    (net (code "224") (name "SHIFT") (class "Default")
      (node (ref "E19") (pin "3") (pinfunction "I1_3") (pintype "input"))
      (node (ref "E36") (pin "12") (pinfunction "A2_12") (pintype "output"))
    )
    (net (code "225") (name "SKIPL") (class "Default")
      (node (ref "C46") (pin "P2") (pinfunction "IN1_P2") (pintype "input"))
      (node (ref "C48") (pin "S1") (pinfunction "P$2_S1") (pintype "bidirectional"))
      (node (ref "C52") (pin "K2") (pinfunction "P$1_K2") (pintype "passive"))
    )
    (net (code "226") (name "STROBE") (class "Default")
      (node (ref "C48") (pin "H2") (pinfunction "P$2_H2") (pintype "bidirectional"))
      (node (ref "C50") (pin "L1") (pinfunction "IN1_L1") (pintype "input"))
      (node (ref "C50") (pin "M1") (pinfunction "IN2_M1") (pintype "input"))
      (node (ref "D31") (pin "M1") (pinfunction "OUT_M1") (pintype "output"))
    )
    (net (code "227") (name "T2") (class "Default")
      (node (ref "A04") (pin "T2") (pinfunction "P$2_T2") (pintype "bidirectional"))
      (node (ref "D04") (pin "T2") (pinfunction "P$2_T2") (pintype "bidirectional"))
    )
    (net (code "228") (name "TP3") (class "Default")
      (node (ref "C51") (pin "H2") (pinfunction "H2_H2") (pintype "input"))
      (node (ref "D31") (pin "B1") (pinfunction "OUT_B1") (pintype "output"))
      (node (ref "E11") (pin "9") (pinfunction "I0_9") (pintype "input"))
      (node (ref "U$2") (pin "CH2") (pinfunction "1_CH2") (pintype "bidirectional"))
    )
    (net (code "229") (name "TP4") (class "Default")
      (node (ref "C48") (pin "J2") (pinfunction "P$2_J2") (pintype "bidirectional"))
      (node (ref "D31") (pin "E1") (pinfunction "OUT_E1") (pintype "output"))
      (node (ref "E11") (pin "4") (pinfunction "I0_4") (pintype "input"))
      (node (ref "U$2") (pin "CJ2") (pinfunction "1_CJ2") (pintype "bidirectional"))
    )
    (net (code "230") (name "V2") (class "Default")
      (node (ref "A04") (pin "V2") (pinfunction "P$2_V2") (pintype "bidirectional"))
      (node (ref "D04") (pin "V2") (pinfunction "P$2_V2") (pintype "bidirectional"))
    )
    (net (code "231") (name "VCC") (class "Default")
      (node (ref "C1") (pin "1") (pinfunction "1_1") (pintype "passive"))
      (node (ref "C10") (pin "1") (pinfunction "1_1") (pintype "passive"))
      (node (ref "C11") (pin "1") (pinfunction "1_1") (pintype "passive"))
      (node (ref "C12") (pin "1") (pinfunction "1_1") (pintype "passive"))
      (node (ref "C13") (pin "1") (pinfunction "1_1") (pintype "passive"))
      (node (ref "C14") (pin "1") (pinfunction "1_1") (pintype "passive"))
      (node (ref "C15") (pin "1") (pinfunction "1_1") (pintype "passive"))
      (node (ref "C16") (pin "1") (pinfunction "1_1") (pintype "passive"))
      (node (ref "C17") (pin "1") (pinfunction "1_1") (pintype "passive"))
      (node (ref "C18") (pin "1") (pinfunction "1_1") (pintype "passive"))
      (node (ref "C19") (pin "1") (pinfunction "1_1") (pintype "passive"))
      (node (ref "C2") (pin "1") (pinfunction "1_1") (pintype "passive"))
      (node (ref "C20") (pin "1") (pinfunction "1_1") (pintype "passive"))
      (node (ref "C21") (pin "1") (pinfunction "1_1") (pintype "passive"))
      (node (ref "C22") (pin "1") (pinfunction "1_1") (pintype "passive"))
      (node (ref "C23") (pin "1") (pinfunction "1_1") (pintype "passive"))
      (node (ref "C24") (pin "1") (pinfunction "1_1") (pintype "passive"))
      (node (ref "C25") (pin "1") (pinfunction "1_1") (pintype "passive"))
      (node (ref "C26") (pin "1") (pinfunction "1_1") (pintype "passive"))
      (node (ref "C27") (pin "1") (pinfunction "1_1") (pintype "passive"))
      (node (ref "C28") (pin "1") (pinfunction "1_1") (pintype "passive"))
      (node (ref "C29") (pin "1") (pinfunction "1_1") (pintype "passive"))
      (node (ref "C3") (pin "1") (pinfunction "1_1") (pintype "passive"))
      (node (ref "C30") (pin "1") (pinfunction "1_1") (pintype "passive"))
      (node (ref "C31") (pin "1") (pinfunction "1_1") (pintype "passive"))
      (node (ref "C32") (pin "1") (pinfunction "1_1") (pintype "passive"))
      (node (ref "C33") (pin "1") (pinfunction "1_1") (pintype "passive"))
      (node (ref "C34") (pin "1") (pinfunction "1_1") (pintype "passive"))
      (node (ref "C35") (pin "1") (pinfunction "1_1") (pintype "passive"))
      (node (ref "C36") (pin "1") (pinfunction "1_1") (pintype "passive"))
      (node (ref "C37") (pin "1") (pinfunction "1_1") (pintype "passive"))
      (node (ref "C38") (pin "1") (pinfunction "1_1") (pintype "passive"))
      (node (ref "C39") (pin "1") (pinfunction "1_1") (pintype "passive"))
      (node (ref "C4") (pin "1") (pinfunction "1_1") (pintype "passive"))
      (node (ref "C40") (pin "1") (pinfunction "1_1") (pintype "passive"))
      (node (ref "C41") (pin "1") (pinfunction "1_1") (pintype "passive"))
      (node (ref "C42") (pin "+") (pinfunction "+_+") (pintype "passive"))
      (node (ref "C43") (pin "+") (pinfunction "+_+") (pintype "passive"))
      (node (ref "C44") (pin "+") (pinfunction "+_+") (pintype "passive"))
      (node (ref "C45") (pin "+") (pinfunction "+_+") (pintype "passive"))
      (node (ref "C5") (pin "1") (pinfunction "1_1") (pintype "passive"))
      (node (ref "C6") (pin "1") (pinfunction "1_1") (pintype "passive"))
      (node (ref "C7") (pin "1") (pinfunction "1_1") (pintype "passive"))
      (node (ref "C8") (pin "1") (pinfunction "1_1") (pintype "passive"))
      (node (ref "C9") (pin "1") (pinfunction "1_1") (pintype "passive"))
      (node (ref "R1") (pin "2") (pinfunction "2_2") (pintype "passive"))
      (node (ref "R19") (pin "1") (pinfunction "1_1") (pintype "passive"))
      (node (ref "R2") (pin "2") (pinfunction "2_2") (pintype "passive"))
      (node (ref "R20") (pin "2") (pinfunction "2_2") (pintype "passive"))
      (node (ref "R3") (pin "2") (pinfunction "2_2") (pintype "passive"))
      (node (ref "R4") (pin "2") (pinfunction "2_2") (pintype "passive"))
      (node (ref "R5") (pin "2") (pinfunction "2_2") (pintype "passive"))
      (node (ref "R6") (pin "2") (pinfunction "2_2") (pintype "passive"))
      (node (ref "R7") (pin "2") (pinfunction "2_2") (pintype "passive"))
      (node (ref "R8") (pin "2") (pinfunction "2_2") (pintype "passive"))
      (node (ref "R9") (pin "2") (pinfunction "2_2") (pintype "passive"))
      (node (ref "U$2") (pin "AA2") (pinfunction "1_AA2") (pintype "bidirectional"))
      (node (ref "U$2") (pin "BA2") (pinfunction "1_BA2") (pintype "bidirectional"))
      (node (ref "U$2") (pin "CA2") (pinfunction "1_CA2") (pintype "bidirectional"))
    )
    (net (code "232") (name "WRT") (class "Default")
      (node (ref "E10") (pin "5") (pinfunction "I2_5") (pintype "input"))
      (node (ref "E14") (pin "5") (pinfunction "I0_5") (pintype "input"))
      (node (ref "E24") (pin "10") (pinfunction "I1_10") (pintype "input"))
      (node (ref "E32") (pin "2") (pinfunction "O_2") (pintype "output"))
    )
    (net (code "233") (name "XFER_IOT") (class "Default")
      (node (ref "E10") (pin "1") (pinfunction "I0_1") (pintype "input"))
      (node (ref "E12") (pin "12") (pinfunction "I0_12") (pintype "input"))
      (node (ref "E28") (pin "9") (pinfunction "I0_9") (pintype "input"))
      (node (ref "E38") (pin "6") (pinfunction "O_6") (pintype "output"))
    )
    (net (code "234") (name "XFER_REQ") (class "Default")
      (node (ref "E30") (pin "3") (pinfunction "CLK_3") (pintype "input"))
      (node (ref "E36") (pin "4") (pinfunction "A2_4") (pintype "output"))
      (node (ref "E39") (pin "12") (pinfunction "I1_12") (pintype "input"))
    )
    (net (code "235") (name "unconnected-(C51-PadJ2)") (class "Default")
      (node (ref "C51") (pin "J2") (pinfunction "J2_J2") (pintype "output"))
    )
    (net (code "236") (name "unconnected-(C51-PadK2)") (class "Default")
      (node (ref "C51") (pin "K2") (pinfunction "K2_K2") (pintype "output"))
    )
    (net (code "237") (name "unconnected-(C51-PadL2)") (class "Default")
      (node (ref "C51") (pin "L2") (pinfunction "L2_L2") (pintype "output"))
    )
    (net (code "238") (name "unconnected-(C51-PadM2)") (class "Default")
      (node (ref "C51") (pin "M2") (pinfunction "M2_M2") (pintype "output"))
    )
    (net (code "239") (name "unconnected-(C51-PadN2)") (class "Default")
      (node (ref "C51") (pin "N2") (pinfunction "N2_N2") (pintype "output"))
    )
    (net (code "240") (name "unconnected-(C51-PadP2)") (class "Default")
      (node (ref "C51") (pin "P2") (pinfunction "P2_P2") (pintype "output"))
    )
    (net (code "241") (name "unconnected-(C51-PadR2)") (class "Default")
      (node (ref "C51") (pin "R2") (pinfunction "R2_R2") (pintype "output"))
    )
    (net (code "242") (name "unconnected-(C51-PadS2)") (class "Default")
      (node (ref "C51") (pin "S2") (pinfunction "S2_S2") (pintype "output"))
    )
    (net (code "243") (name "unconnected-(C51-PadU2)") (class "Default")
      (node (ref "C51") (pin "U2") (pinfunction "U2_U2") (pintype "output"))
    )
    (net (code "244") (name "unconnected-(C51-PadV2)") (class "Default")
      (node (ref "C51") (pin "V2") (pinfunction "V2_V2") (pintype "output"))
    )
    (net (code "245") (name "unconnected-(E4A-QA-Pad14)") (class "Default")
      (node (ref "E4") (pin "14") (pinfunction "QA_14") (pintype "output"))
    )
    (net (code "246") (name "unconnected-(E4A-QB-Pad13)") (class "Default")
      (node (ref "E4") (pin "13") (pinfunction "QB_13") (pintype "output"))
    )
    (net (code "247") (name "unconnected-(E4A-QC-Pad12)") (class "Default")
      (node (ref "E4") (pin "12") (pinfunction "QC_12") (pintype "output"))
    )
    (net (code "248") (name "unconnected-(E4A-QD-Pad11)") (class "Default")
      (node (ref "E4") (pin "11") (pinfunction "QD_11") (pintype "output"))
    )
    (net (code "249") (name "unconnected-(E7A-~{Q}-Pad6)") (class "Default")
      (node (ref "E7") (pin "6") (pinfunction "~{Q}_6") (pintype "output"))
    )
    (net (code "250") (name "unconnected-(E9A-~{QD}-Pad12)") (class "Default")
      (node (ref "E9") (pin "12") (pinfunction "~{QD}_12") (pintype "output"))
    )
    (net (code "251") (name "unconnected-(E15A-~{Q}-Pad6)") (class "Default")
      (node (ref "E15") (pin "6") (pinfunction "~{Q}_6") (pintype "output"))
    )
    (net (code "252") (name "unconnected-(E15B-~{Q}-Pad8)") (class "Default")
      (node (ref "E15") (pin "8") (pinfunction "~{Q}_8") (pintype "output"))
    )
    (net (code "253") (name "unconnected-(E21A-~{QD}-Pad12)") (class "Default")
      (node (ref "E21") (pin "12") (pinfunction "~{QD}_12") (pintype "output"))
    )
    (net (code "254") (name "unconnected-(E22A-~{Q}-Pad6)") (class "Default")
      (node (ref "E22") (pin "6") (pinfunction "~{Q}_6") (pintype "output"))
    )
    (net (code "255") (name "unconnected-(E22B-~{Q}-Pad8)") (class "Default")
      (node (ref "E22") (pin "8") (pinfunction "~{Q}_8") (pintype "output"))
    )
    (net (code "256") (name "unconnected-(E26A-~{Q}-Pad6)") (class "Default")
      (node (ref "E26") (pin "6") (pinfunction "~{Q}_6") (pintype "output"))
    )
    (net (code "257") (name "unconnected-(E26B-~{Q}-Pad8)") (class "Default")
      (node (ref "E26") (pin "8") (pinfunction "~{Q}_8") (pintype "output"))
    )
    (net (code "258") (name "unconnected-(E27A-Q-Pad15)") (class "Default")
      (node (ref "E27") (pin "15") (pinfunction "Q_15") (pintype "output"))
    )
    (net (code "259") (name "unconnected-(E30A-~{Q}-Pad6)") (class "Default")
      (node (ref "E30") (pin "6") (pinfunction "~{Q}_6") (pintype "output"))
    )
    (net (code "260") (name "unconnected-(E30B-~{Q}-Pad8)") (class "Default")
      (node (ref "E30") (pin "8") (pinfunction "~{Q}_8") (pintype "output"))
    )
    (net (code "261") (name "unconnected-(E31-Pad7)") (class "Default")
      (node (ref "E31") (pin "7") (pinfunction "7_7") (pintype "passive"))
    )
    (net (code "262") (name "unconnected-(E31-Pad8)") (class "Default")
      (node (ref "E31") (pin "8") (pinfunction "8_8") (pintype "passive"))
    )
    (net (code "263") (name "unconnected-(E31-Pad9)") (class "Default")
      (node (ref "E31") (pin "9") (pinfunction "9_9") (pintype "passive"))
    )
    (net (code "264") (name "unconnected-(E31-Pad10)") (class "Default")
      (node (ref "E31") (pin "10") (pinfunction "10_10") (pintype "passive"))
    )
    (net (code "265") (name "unconnected-(E33A-~{QD}-Pad12)") (class "Default")
      (node (ref "E33") (pin "12") (pinfunction "~{QD}_12") (pintype "output"))
    )
    (net (code "266") (name "unconnected-(E41A-O0-Pad1)") (class "Default")
      (node (ref "E41") (pin "1") (pinfunction "O0_1") (pintype "output"))
    )
    (net (code "267") (name "unconnected-(E41A-O8-Pad10)") (class "Default")
      (node (ref "E41") (pin "10") (pinfunction "O8_10") (pintype "output"))
    )
    (net (code "268") (name "unconnected-(E41A-O9-Pad11)") (class "Default")
      (node (ref "E41") (pin "11") (pinfunction "O9_11") (pintype "output"))
    )
    (net (code "269") (name "~{BINIT}") (class "Default")
      (node (ref "E15") (pin "1") (pinfunction "CLR_1") (pintype "input"))
      (node (ref "E22") (pin "13") (pinfunction "CLR_13") (pintype "input"))
      (node (ref "E26") (pin "13") (pinfunction "CLR_13") (pintype "input"))
      (node (ref "E30") (pin "13") (pinfunction "CLR_13") (pintype "input"))
      (node (ref "E32") (pin "4") (pinfunction "O_4") (pintype "output"))
    )
    (net (code "270") (name "~{C0}") (class "Default")
      (node (ref "E14") (pin "1") (pinfunction "O_1") (pintype "open_collector"))
      (node (ref "U$2") (pin "CE1") (pinfunction "1_CE1") (pintype "bidirectional"))
    )
    (net (code "271") (name "~{C1}") (class "Default")
      (node (ref "E14") (pin "13") (pinfunction "O_13") (pintype "open_collector"))
      (node (ref "U$2") (pin "CH1") (pinfunction "1_CH1") (pintype "bidirectional"))
    )
    (net (code "272") (name "~{CLK_BUF}") (class "Default")
      (node (ref "E21") (pin "6") (pinfunction "CLK_6") (pintype "input"))
      (node (ref "E33") (pin "6") (pinfunction "CLK_6") (pintype "input"))
      (node (ref "E8") (pin "12") (pinfunction "O_12") (pintype "output"))
      (node (ref "E9") (pin "6") (pinfunction "CLK_6") (pintype "input"))
    )
    (net (code "273") (name "~{CLK_PARITY}") (class "Default")
      (node (ref "E19") (pin "1") (pinfunction "O_1") (pintype "output"))
      (node (ref "E27") (pin "1") (pinfunction "CLK_1") (pintype "input"))
      (node (ref "E8") (pin "3") (pinfunction "I_3") (pintype "input"))
    )
    (net (code "274") (name "~{DATA0}") (class "Default")
      (node (ref "E1") (pin "15") (pinfunction "Y3_15") (pintype "input"))
      (node (ref "E5") (pin "1") (pinfunction "O_1") (pintype "open_collector"))
      (node (ref "U$2") (pin "AR1") (pinfunction "1_AR1") (pintype "bidirectional"))
    )
    (net (code "275") (name "~{DATA1}") (class "Default")
      (node (ref "E1") (pin "13") (pinfunction "Y2_13") (pintype "input"))
      (node (ref "E5") (pin "4") (pinfunction "O_4") (pintype "open_collector"))
      (node (ref "U$2") (pin "AS1") (pinfunction "1_AS1") (pintype "bidirectional"))
    )
    (net (code "276") (name "~{DATA2}") (class "Default")
      (node (ref "E1") (pin "11") (pinfunction "Y1_11") (pintype "input"))
      (node (ref "E5") (pin "10") (pinfunction "O_10") (pintype "open_collector"))
      (node (ref "U$2") (pin "AU1") (pinfunction "1_AU1") (pintype "bidirectional"))
    )
    (net (code "277") (name "~{DATA3}") (class "Default")
      (node (ref "E1") (pin "5") (pinfunction "Y3_5") (pintype "input"))
      (node (ref "E5") (pin "13") (pinfunction "O_13") (pintype "open_collector"))
      (node (ref "U$2") (pin "AV1") (pinfunction "1_AV1") (pintype "bidirectional"))
    )
    (net (code "278") (name "~{DATA4}") (class "Default")
      (node (ref "E1") (pin "3") (pinfunction "Y2_3") (pintype "input"))
      (node (ref "E17") (pin "1") (pinfunction "O_1") (pintype "open_collector"))
      (node (ref "U$2") (pin "BR1") (pinfunction "1_BR1") (pintype "bidirectional"))
    )
    (net (code "279") (name "~{DATA5}") (class "Default")
      (node (ref "E1") (pin "1") (pinfunction "Y1_1") (pintype "input"))
      (node (ref "E17") (pin "4") (pinfunction "O_4") (pintype "open_collector"))
      (node (ref "U$2") (pin "BS1") (pinfunction "1_BS1") (pintype "bidirectional"))
    )
    (net (code "280") (name "~{DATA6}") (class "Default")
      (node (ref "E17") (pin "10") (pinfunction "O_10") (pintype "open_collector"))
      (node (ref "E25") (pin "15") (pinfunction "Y3_15") (pintype "input"))
      (node (ref "U$2") (pin "BU1") (pinfunction "1_BU1") (pintype "bidirectional"))
    )
    (net (code "281") (name "~{DATA7}") (class "Default")
      (node (ref "E17") (pin "13") (pinfunction "O_13") (pintype "open_collector"))
      (node (ref "E25") (pin "13") (pinfunction "Y2_13") (pintype "input"))
      (node (ref "U$2") (pin "BV1") (pinfunction "1_BV1") (pintype "bidirectional"))
    )
    (net (code "282") (name "~{DATA8}") (class "Default")
      (node (ref "E25") (pin "11") (pinfunction "Y1_11") (pintype "input"))
      (node (ref "E29") (pin "1") (pinfunction "O_1") (pintype "open_collector"))
      (node (ref "U$2") (pin "DR1") (pinfunction "1_DR1") (pintype "bidirectional"))
    )
    (net (code "283") (name "~{DATA9}") (class "Default")
      (node (ref "E25") (pin "5") (pinfunction "Y3_5") (pintype "input"))
      (node (ref "E29") (pin "4") (pinfunction "O_4") (pintype "open_collector"))
      (node (ref "U$2") (pin "DS1") (pinfunction "1_DS1") (pintype "bidirectional"))
    )
    (net (code "284") (name "~{DATA10}") (class "Default")
      (node (ref "E25") (pin "3") (pinfunction "Y2_3") (pintype "input"))
      (node (ref "E29") (pin "10") (pinfunction "O_10") (pintype "open_collector"))
      (node (ref "U$2") (pin "DU1") (pinfunction "1_DU1") (pintype "bidirectional"))
    )
    (net (code "285") (name "~{DATA11}") (class "Default")
      (node (ref "E25") (pin "1") (pinfunction "Y1_1") (pintype "input"))
      (node (ref "E29") (pin "13") (pinfunction "O_13") (pintype "open_collector"))
      (node (ref "U$2") (pin "DV1") (pinfunction "1_DV1") (pintype "bidirectional"))
    )
    (net (code "286") (name "~{DONE_SKIP}") (class "Default")
      (node (ref "E10") (pin "11") (pinfunction "I2_11") (pintype "input"))
      (node (ref "E19") (pin "9") (pinfunction "I1_9") (pintype "input"))
      (node (ref "E34") (pin "11") (pinfunction "O_11") (pintype "output"))
      (node (ref "U$2") (pin "CB1") (pinfunction "1_CB1") (pintype "bidirectional"))
    )
    (net (code "287") (name "~{DONE}") (class "Default")
      (node (ref "E10") (pin "4") (pinfunction "I1_4") (pintype "input"))
      (node (ref "E28") (pin "10") (pinfunction "I1_10") (pintype "input"))
      (node (ref "E32") (pin "8") (pinfunction "O_8") (pintype "output"))
    )
    (net (code "288") (name "~{ENB_BUF_LD}") (class "Default")
      (node (ref "E16") (pin "11") (pinfunction "O_11") (pintype "output"))
      (node (ref "E20") (pin "13") (pinfunction "I2_13") (pintype "input"))
      (node (ref "E21") (pin "13") (pinfunction "SHF_13") (pintype "input"))
      (node (ref "E33") (pin "13") (pinfunction "SHF_13") (pintype "input"))
      (node (ref "E4") (pin "9") (pinfunction "LD_9") (pintype "input"))
      (node (ref "E9") (pin "13") (pinfunction "SHF_13") (pintype "input"))
    )
    (net (code "289") (name "~{ERR_SKIP}") (class "Default")
      (node (ref "E10") (pin "10") (pinfunction "I1_10") (pintype "input"))
      (node (ref "E23") (pin "9") (pinfunction "I1_9") (pintype "input"))
      (node (ref "E34") (pin "3") (pinfunction "O_3") (pintype "output"))
    )
    (net (code "290") (name "~{INIT_IOT}") (class "Default")
      (node (ref "E41") (pin "9") (pinfunction "O7_9") (pintype "output"))
      (node (ref "E7") (pin "2") (pinfunction "D_2") (pintype "input"))
    )
    (net (code "291") (name "~{INIT}") (class "Default")
      (node (ref "E16") (pin "10") (pinfunction "I1_10") (pintype "input"))
      (node (ref "E2") (pin "1") (pinfunction "CLR_1") (pintype "input"))
      (node (ref "E2") (pin "13") (pinfunction "CLR_13") (pintype "input"))
      (node (ref "E21") (pin "1") (pinfunction "CLR_1") (pintype "input"))
      (node (ref "E33") (pin "1") (pinfunction "CLR_1") (pintype "input"))
      (node (ref "E4") (pin "1") (pinfunction "CLR_1") (pintype "input"))
      (node (ref "E8") (pin "6") (pinfunction "O_6") (pintype "output"))
      (node (ref "E9") (pin "1") (pinfunction "CLR_1") (pintype "input"))
    )
    (net (code "292") (name "~{INTERNAL_IO}") (class "Default")
      (node (ref "E18") (pin "1") (pinfunction "O_1") (pintype "open_collector"))
      (node (ref "U$2") (pin "CL1") (pinfunction "1_CL1") (pintype "bidirectional"))
    )
    (net (code "293") (name "~{INTR_IOT}") (class "Default")
      (node (ref "E41") (pin "7") (pinfunction "O6_7") (pintype "output"))
      (node (ref "E6") (pin "6") (pinfunction "I1_6") (pintype "input"))
    )
    (net (code "294") (name "~{INT_RQST}") (class "Default")
      (node (ref "E18") (pin "4") (pinfunction "O_4") (pintype "open_collector"))
      (node (ref "U$2") (pin "CP1") (pinfunction "1_CP1") (pintype "bidirectional"))
    )
    (net (code "295") (name "~{IO_PAUSE}") (class "Default")
      (node (ref "E39") (pin "6") (pinfunction "I0_6") (pintype "input"))
      (node (ref "U$2") (pin "CD1") (pinfunction "1_CD1") (pintype "bidirectional"))
    )
    (net (code "296") (name "~{LCD_IOT}") (class "Default")
      (node (ref "E12") (pin "4") (pinfunction "I0_4") (pintype "input"))
      (node (ref "E16") (pin "5") (pinfunction "I1_5") (pintype "input"))
      (node (ref "E38") (pin "3") (pinfunction "I_3") (pintype "input"))
      (node (ref "E41") (pin "2") (pinfunction "O1_2") (pintype "output"))
      (node (ref "E6") (pin "3") (pinfunction "I1_3") (pintype "input"))
    )
    (net (code "297") (name "~{MAINT}") (class "Default")
      (node (ref "E10") (pin "3") (pinfunction "I0_3") (pintype "input"))
      (node (ref "E16") (pin "12") (pinfunction "I0_12") (pintype "input"))
      (node (ref "E2") (pin "8") (pinfunction "~{Q}_8") (pintype "output"))
      (node (ref "E22") (pin "4") (pinfunction "PRE_4") (pintype "input"))
      (node (ref "E26") (pin "4") (pinfunction "PRE_4") (pintype "input"))
      (node (ref "E28") (pin "1") (pinfunction "I0_1") (pintype "input"))
      (node (ref "E28") (pin "12") (pinfunction "I2_12") (pintype "input"))
      (node (ref "E30") (pin "4") (pinfunction "PRE_4") (pintype "input"))
      (node (ref "E32") (pin "11") (pinfunction "I_11") (pintype "input"))
    )
    (net (code "298") (name "~{MD03}") (class "Default")
      (node (ref "E35") (pin "4") (pinfunction "I0_4") (pintype "input"))
      (node (ref "U$2") (pin "AP1") (pinfunction "1_AP1") (pintype "bidirectional"))
    )
    (net (code "299") (name "~{MD04}") (class "Default")
      (node (ref "E35") (pin "6") (pinfunction "I2_6") (pintype "input"))
      (node (ref "U$2") (pin "BK1") (pinfunction "1_BK1") (pintype "bidirectional"))
    )
    (net (code "300") (name "~{MD05}") (class "Default")
      (node (ref "E35") (pin "5") (pinfunction "I1_5") (pintype "input"))
      (node (ref "U$2") (pin "BL1") (pinfunction "1_BL1") (pintype "bidirectional"))
    )
    (net (code "301") (name "~{MD06}") (class "Default")
      (node (ref "E31") (pin "4") (pinfunction "4_4") (pintype "passive"))
      (node (ref "E40") (pin "1") (pinfunction "Y1_1") (pintype "input"))
      (node (ref "U$2") (pin "BM1") (pinfunction "1_BM1") (pintype "bidirectional"))
    )
    (net (code "302") (name "~{MD07}") (class "Default")
      (node (ref "E31") (pin "5") (pinfunction "5_5") (pintype "passive"))
      (node (ref "E40") (pin "3") (pinfunction "Y2_3") (pintype "input"))
      (node (ref "U$2") (pin "BP1") (pinfunction "1_BP1") (pintype "bidirectional"))
    )
    (net (code "303") (name "~{MD08}") (class "Default")
      (node (ref "E31") (pin "6") (pinfunction "6_6") (pintype "passive"))
      (node (ref "E40") (pin "5") (pinfunction "Y3_5") (pintype "input"))
      (node (ref "U$2") (pin "DK1") (pinfunction "1_DK1") (pintype "bidirectional"))
    )
    (net (code "304") (name "~{MD09}") (class "Default")
      (node (ref "E40") (pin "15") (pinfunction "Y3_15") (pintype "input"))
      (node (ref "U$2") (pin "DL1") (pinfunction "1_DL1") (pintype "bidirectional"))
    )
    (net (code "305") (name "~{MD10}") (class "Default")
      (node (ref "E40") (pin "13") (pinfunction "Y2_13") (pintype "input"))
      (node (ref "U$2") (pin "DM1") (pinfunction "1_DM1") (pintype "bidirectional"))
    )
    (net (code "306") (name "~{MD11}") (class "Default")
      (node (ref "E40") (pin "11") (pinfunction "Y1_11") (pintype "input"))
      (node (ref "U$2") (pin "DP1") (pinfunction "1_DP1") (pintype "bidirectional"))
    )
    (net (code "307") (name "~{PARITY}") (class "Default")
      (node (ref "E24") (pin "12") (pinfunction "I0_12") (pintype "input"))
      (node (ref "E27") (pin "14") (pinfunction "~{Q}_14") (pintype "output"))
    )
    (net (code "308") (name "~{RX8_SEL}") (class "Default")
      (node (ref "E1") (pin "7") (pinfunction "FORCE0_7") (pintype "input"))
      (node (ref "E1") (pin "9") (pinfunction "FORCE0_9") (pintype "input"))
      (node (ref "E25") (pin "7") (pinfunction "FORCE0_7") (pintype "input"))
      (node (ref "E25") (pin "9") (pinfunction "FORCE0_9") (pintype "input"))
      (node (ref "E32") (pin "6") (pinfunction "O_6") (pintype "output"))
    )
    (net (code "309") (name "~{RX_12_BIT}") (class "Default")
      (node (ref "DRIVE") (pin "FF") (pinfunction "28_FF") (pintype "bidirectional"))
      (node (ref "E14") (pin "10") (pinfunction "O_10") (pintype "open_collector"))
      (node (ref "R16") (pin "2") (pinfunction "2_2") (pintype "passive"))
      (node (ref "R7") (pin "1") (pinfunction "1_1") (pintype "passive"))
    )
    (net (code "310") (name "~{RX_DATA}") (class "Default")
      (node (ref "DRIVE") (pin "BB") (pinfunction "24_BB") (pintype "bidirectional"))
      (node (ref "E14") (pin "4") (pinfunction "O_4") (pintype "open_collector"))
      (node (ref "E36") (pin "11") (pinfunction "Y1_11") (pintype "input"))
      (node (ref "R17") (pin "2") (pinfunction "2_2") (pintype "passive"))
      (node (ref "R8") (pin "1") (pinfunction "1_1") (pintype "passive"))
    )
    (net (code "311") (name "~{RX_DONE}") (class "Default")
      (node (ref "DRIVE") (pin "X") (pinfunction "20_X") (pintype "bidirectional"))
      (node (ref "E36") (pin "5") (pinfunction "Y3_5") (pintype "input"))
      (node (ref "R13") (pin "2") (pinfunction "2_2") (pintype "passive"))
      (node (ref "R4") (pin "1") (pinfunction "1_1") (pintype "passive"))
    )
    (net (code "312") (name "~{RX_ERROR}") (class "Default")
      (node (ref "DRIVE") (pin "J") (pinfunction "8_J") (pintype "bidirectional"))
      (node (ref "E36") (pin "1") (pinfunction "Y1_1") (pintype "input"))
      (node (ref "R14") (pin "2") (pinfunction "2_2") (pintype "passive"))
      (node (ref "R5") (pin "1") (pinfunction "1_1") (pintype "passive"))
    )
    (net (code "313") (name "~{RX_INIT}") (class "Default")
      (node (ref "DRIVE") (pin "N") (pinfunction "12_N") (pintype "bidirectional"))
      (node (ref "E37") (pin "13") (pinfunction "O_13") (pintype "open_collector"))
      (node (ref "R9") (pin "1") (pinfunction "1_1") (pintype "passive"))
    )
    (net (code "314") (name "~{RX_OUT}") (class "Default")
      (node (ref "DRIVE") (pin "RR") (pinfunction "36_RR") (pintype "bidirectional"))
      (node (ref "E36") (pin "15") (pinfunction "Y3_15") (pintype "input"))
      (node (ref "R12") (pin "2") (pinfunction "2_2") (pintype "passive"))
      (node (ref "R3") (pin "1") (pinfunction "1_1") (pintype "passive"))
    )
    (net (code "315") (name "~{RX_RUN}") (class "Default")
      (node (ref "DRIVE") (pin "D") (pinfunction "4_D") (pintype "bidirectional"))
      (node (ref "E18") (pin "13") (pinfunction "O_13") (pintype "open_collector"))
      (node (ref "R15") (pin "2") (pinfunction "2_2") (pintype "passive"))
      (node (ref "R6") (pin "1") (pinfunction "1_1") (pintype "passive"))
    )
    (net (code "316") (name "~{RX_SHIFT}") (class "Default")
      (node (ref "DRIVE") (pin "LL") (pinfunction "32_LL") (pintype "bidirectional"))
      (node (ref "E36") (pin "13") (pinfunction "Y2_13") (pintype "input"))
      (node (ref "R10") (pin "2") (pinfunction "2_2") (pintype "passive"))
      (node (ref "R2") (pin "1") (pinfunction "1_1") (pintype "passive"))
    )
    (net (code "317") (name "~{RX_TR_REQ}") (class "Default")
      (node (ref "DRIVE") (pin "T") (pinfunction "16_T") (pintype "bidirectional"))
      (node (ref "E36") (pin "3") (pinfunction "Y2_3") (pintype "input"))
      (node (ref "R1") (pin "1") (pinfunction "1_1") (pintype "passive"))
      (node (ref "R11") (pin "2") (pinfunction "2_2") (pintype "passive"))
    )
    (net (code "318") (name "~{SDN_IOT}") (class "Default")
      (node (ref "E38") (pin "11") (pinfunction "I_11") (pintype "input"))
      (node (ref "E41") (pin "6") (pinfunction "O5_6") (pintype "output"))
    )
    (net (code "319") (name "~{SER_IOT}") (class "Default")
      (node (ref "E38") (pin "9") (pinfunction "I_9") (pintype "input"))
      (node (ref "E41") (pin "5") (pinfunction "O4_5") (pintype "output"))
    )
    (net (code "320") (name "~{SKIP}") (class "Default")
      (node (ref "E18") (pin "10") (pinfunction "O_10") (pintype "open_collector"))
      (node (ref "U$2") (pin "CS1") (pinfunction "1_CS1") (pintype "bidirectional"))
    )
    (net (code "321") (name "~{STR_IOT}") (class "Default")
      (node (ref "E38") (pin "13") (pinfunction "I_13") (pintype "input"))
      (node (ref "E41") (pin "4") (pinfunction "O3_4") (pintype "output"))
    )
    (net (code "322") (name "~{TP3}") (class "Default")
      (node (ref "E11") (pin "14") (pinfunction "O_14") (pintype "output"))
      (node (ref "E19") (pin "8") (pinfunction "I0_8") (pintype "input"))
      (node (ref "E20") (pin "1") (pinfunction "I0_1") (pintype "input"))
      (node (ref "E23") (pin "11") (pinfunction "I0_11") (pintype "input"))
      (node (ref "E23") (pin "8") (pinfunction "I0_8") (pintype "input"))
      (node (ref "E32") (pin "13") (pinfunction "I_13") (pintype "input"))
      (node (ref "E6") (pin "2") (pinfunction "I0_2") (pintype "input"))
      (node (ref "E6") (pin "5") (pinfunction "I0_5") (pintype "input"))
    )
    (net (code "323") (name "~{TR_SKIP}") (class "Default")
      (node (ref "E10") (pin "9") (pinfunction "I0_9") (pintype "input"))
      (node (ref "E23") (pin "12") (pinfunction "I1_12") (pintype "input"))
      (node (ref "E34") (pin "8") (pinfunction "O_8") (pintype "output"))
      (node (ref "U$2") (pin "DB1") (pinfunction "1_DB1") (pintype "bidirectional"))
    )
    (net (code "324") (name "~{XFER_IOT}") (class "Default")
      (node (ref "E16") (pin "4") (pinfunction "I0_4") (pintype "input"))
      (node (ref "E19") (pin "12") (pinfunction "I1_12") (pintype "input"))
      (node (ref "E38") (pin "5") (pinfunction "I_5") (pintype "input"))
      (node (ref "E41") (pin "3") (pinfunction "O2_3") (pintype "output"))
    )
  )
)
